# Linux_board_va_1.net
KiCad netlist of a schematic drawn in Altium Designer
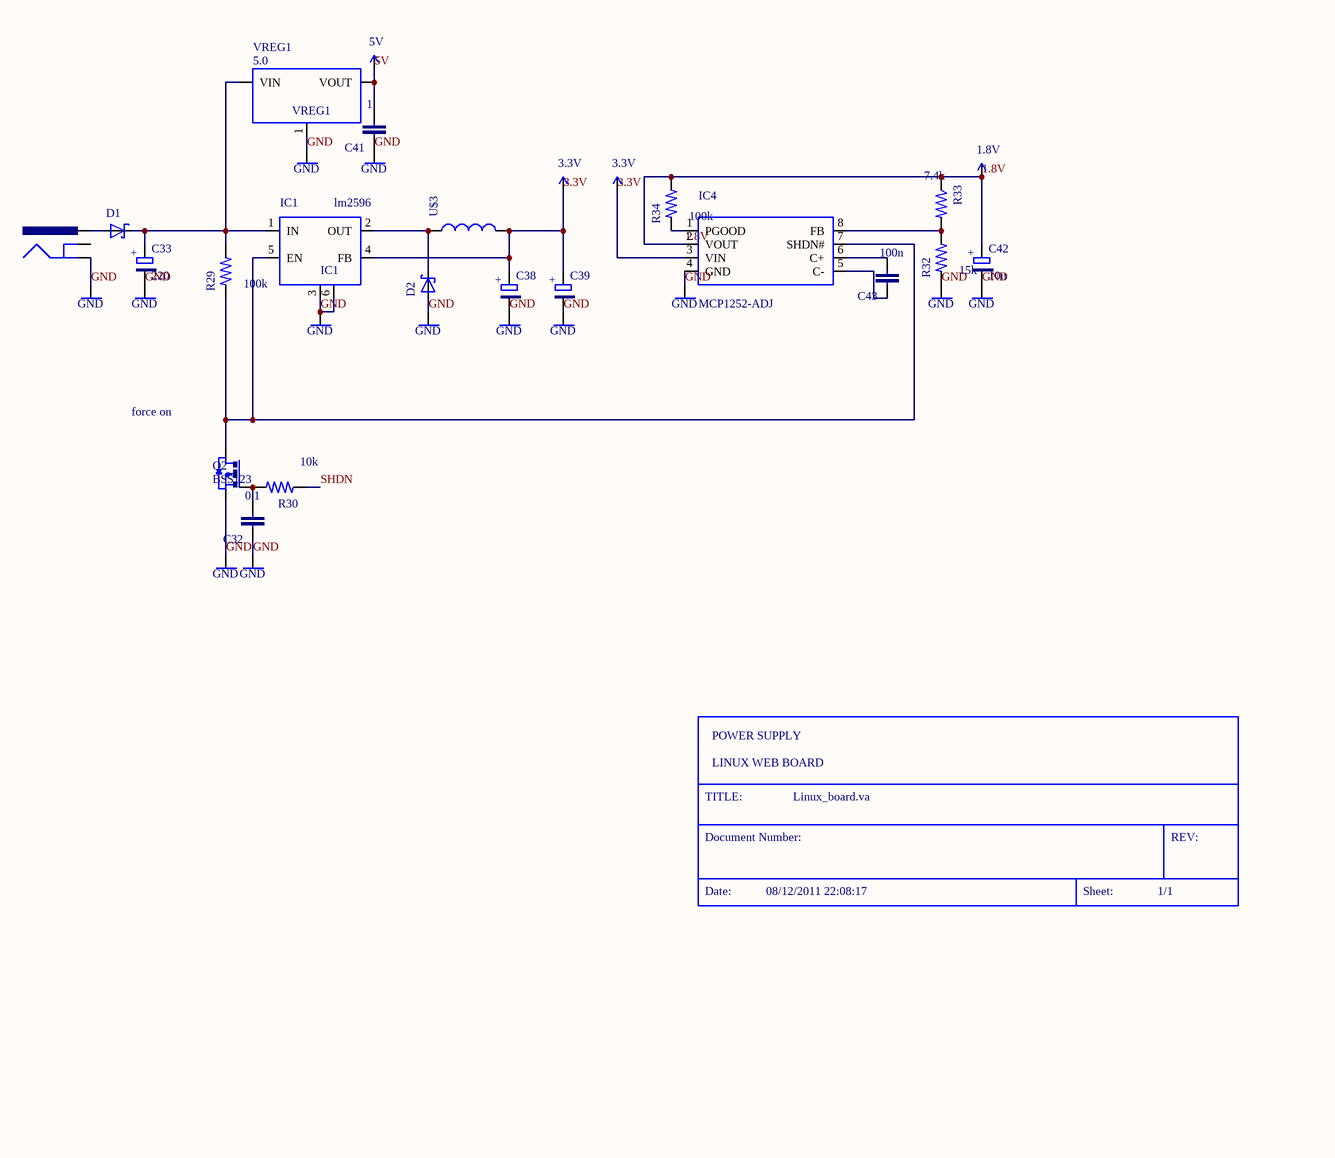
[diagram p0: Linux_board.va_1.SchDoc, top middle]
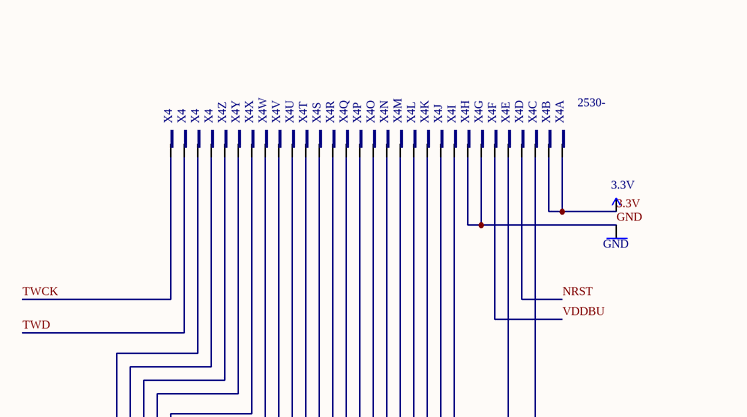
[diagram p1: Linux_board.va_1.SchDoc, top right]
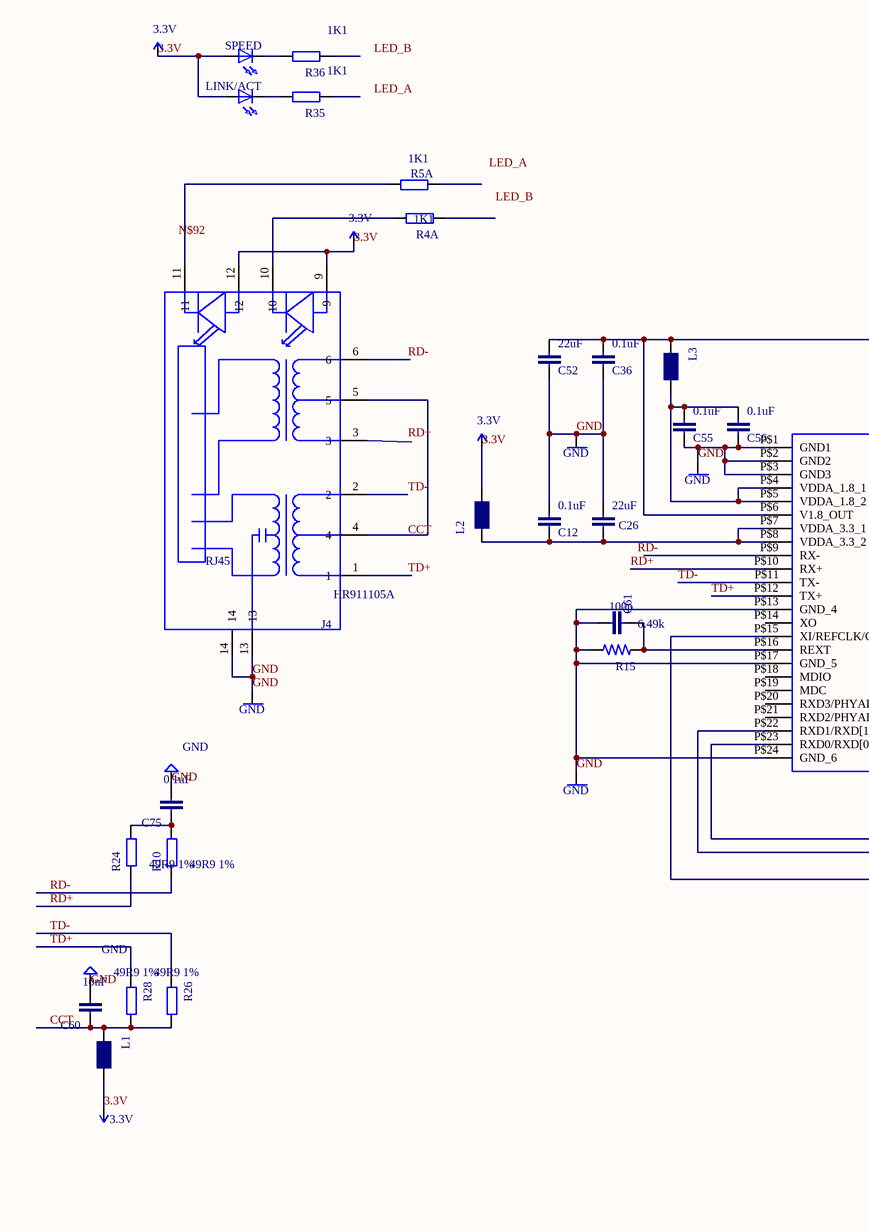
[diagram p2: Linux_board.va_1.SchDoc, bottom left]
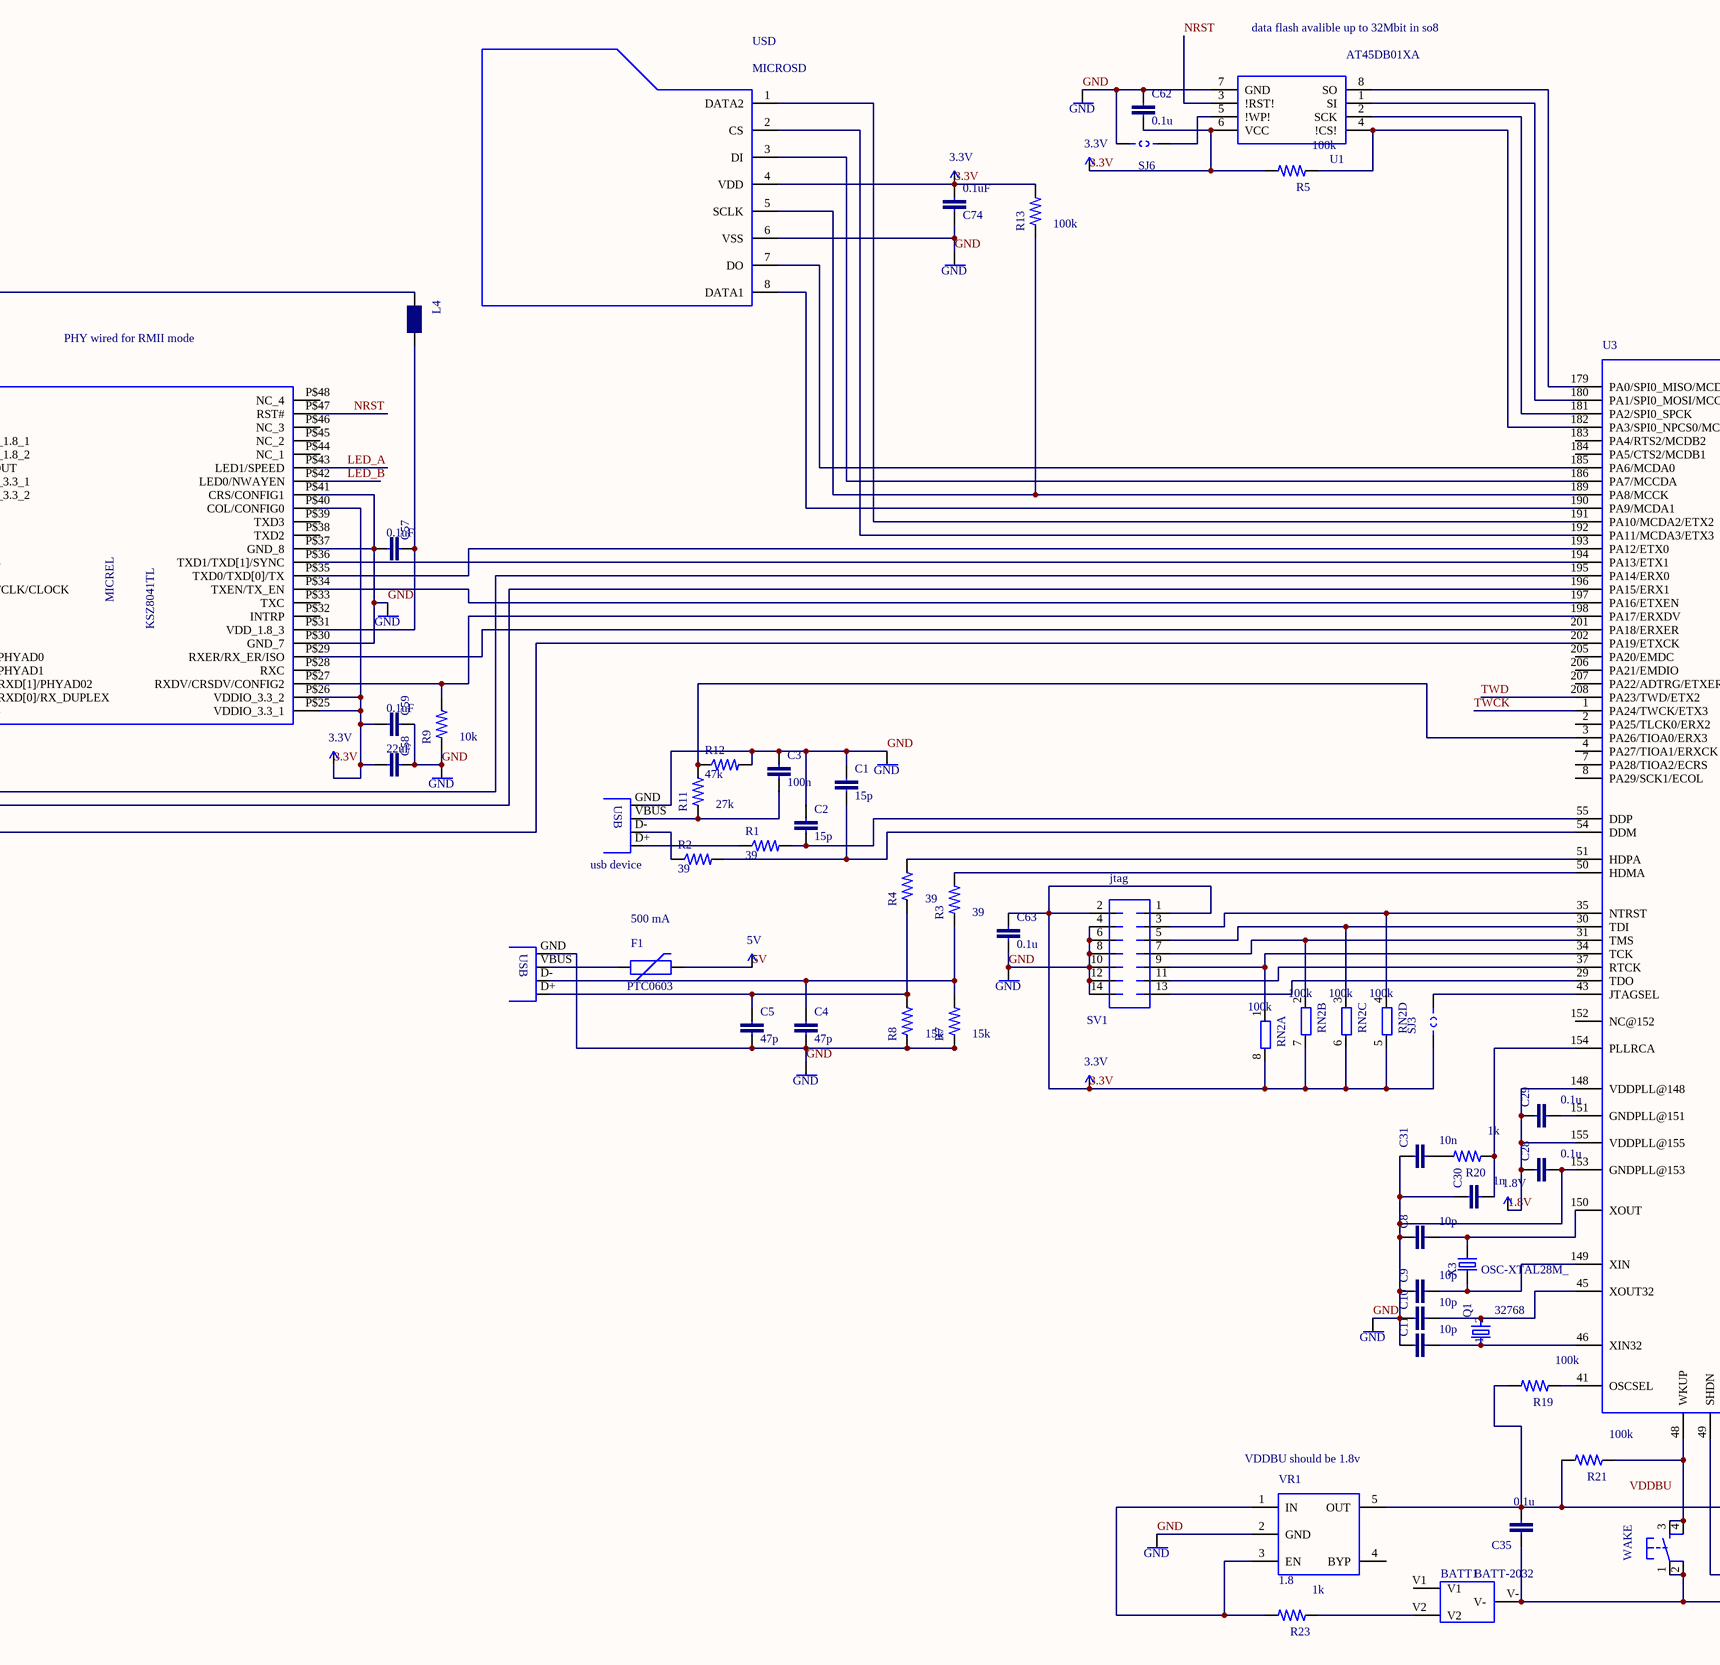
[diagram p3: Linux_board.va_1.SchDoc, bottom middle]
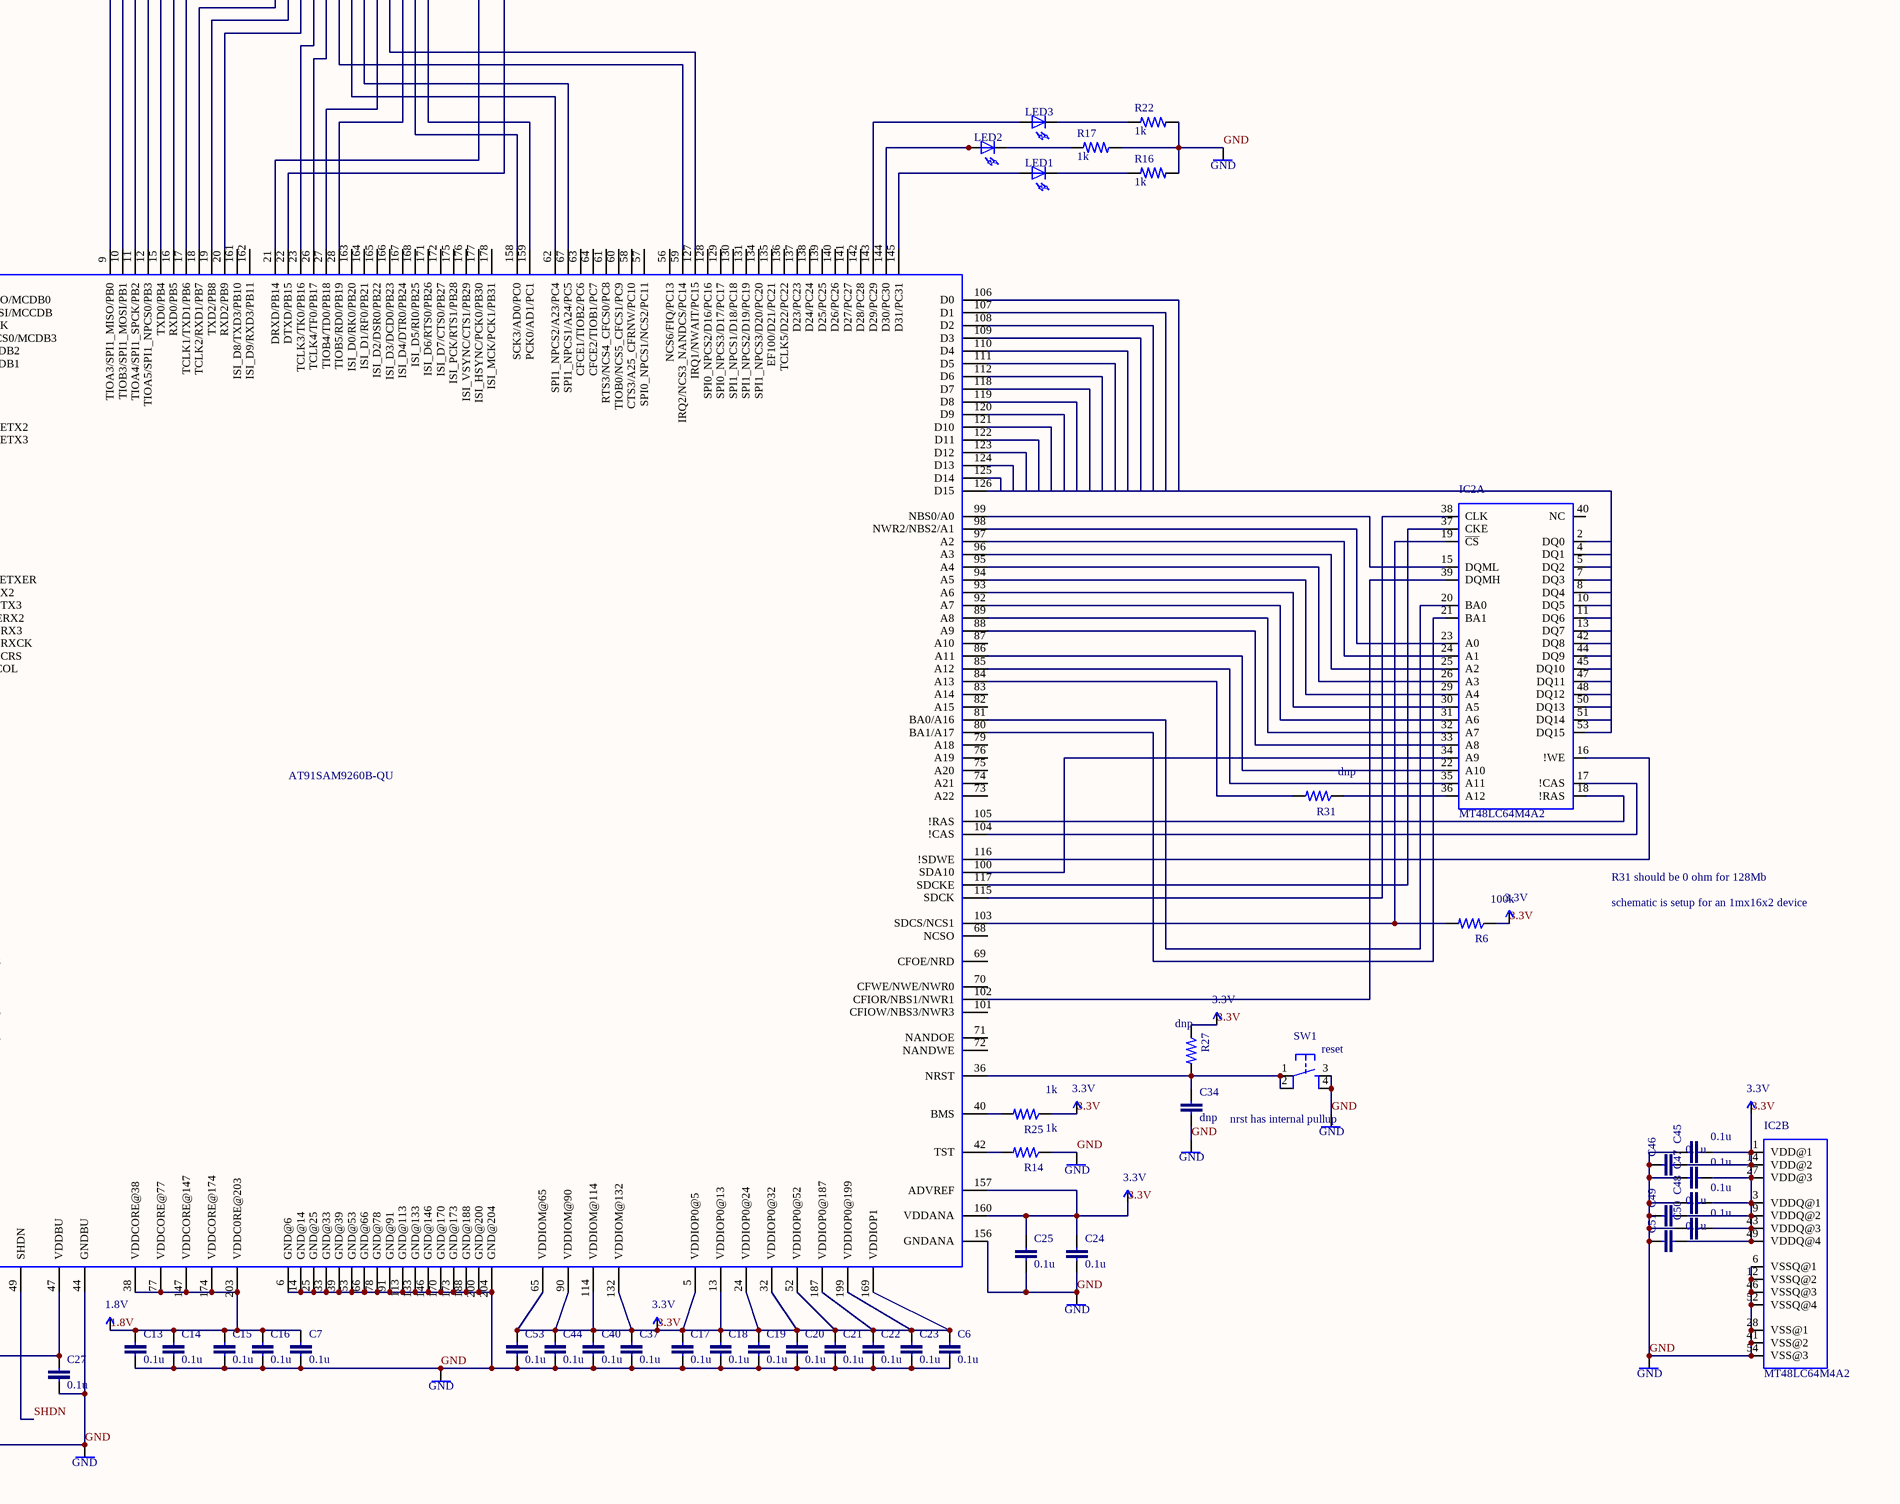
[diagram p4: Linux_board.va_1.SchDoc, bottom right]

(export (version "E")
  (design (tool "Eeschema 10.0.6"))
  (components
    (comp (ref "BATT1")
      (value "BATT-2032")
      (footprint "2032")
      (libsource (lib "dp_devices") (part "BATT-2032"))
    )
    (comp (ref "C1") (value "15p") (footprint "0603-CAP") (libsource (lib "SparkFun") (part "CAP0603-CAP")))
    (comp (ref "C2") (value "15p") (footprint "0603-CAP") (libsource (lib "SparkFun") (part "CAP0603-CAP")))
    (comp (ref "C3") (value "100n") (footprint "0603-CAP") (libsource (lib "SparkFun") (part "CAP0603-CAP")))
    (comp (ref "C4") (value "47p") (footprint "0603-CAP") (libsource (lib "SparkFun") (part "CAP0603-CAP")))
    (comp (ref "C5") (value "47p") (footprint "0603-CAP") (libsource (lib "SparkFun") (part "CAP0603-CAP")))
    (comp (ref "C6") (value "0.1u") (footprint "0603-CAP") (libsource (lib "SparkFun") (part "CAP0603-CAP")))
    (comp (ref "C7") (value "0.1u") (footprint "0603-CAP") (libsource (lib "SparkFun") (part "CAP0603-CAP")))
    (comp (ref "C8") (value "10p") (footprint "0603-CAP") (libsource (lib "SparkFun") (part "CAP0603-CAP")))
    (comp (ref "C9") (value "10p") (footprint "0603-CAP") (libsource (lib "SparkFun") (part "CAP0603-CAP")))
    (comp (ref "C10") (value "10p") (footprint "0603-CAP") (libsource (lib "SparkFun") (part "CAP0603-CAP")))
    (comp (ref "C11") (value "10p") (footprint "0603-CAP") (libsource (lib "SparkFun") (part "CAP0603-CAP")))
    (comp (ref "C12") (value "0.1uF") (footprint "C0603") (libsource (lib "rcl") (part "C-EUC0603")))
    (comp (ref "C13") (value "0.1u") (footprint "0603-CAP") (libsource (lib "SparkFun") (part "CAP0603-CAP")))
    (comp (ref "C14") (value "0.1u") (footprint "0603-CAP") (libsource (lib "SparkFun") (part "CAP0603-CAP")))
    (comp (ref "C15") (value "0.1u") (footprint "0603-CAP") (libsource (lib "SparkFun") (part "CAP0603-CAP")))
    (comp (ref "C16") (value "0.1u") (footprint "0603-CAP") (libsource (lib "SparkFun") (part "CAP0603-CAP")))
    (comp (ref "C17") (value "0.1u") (footprint "0603-CAP") (libsource (lib "SparkFun") (part "CAP0603-CAP")))
    (comp (ref "C18") (value "0.1u") (footprint "0603-CAP") (libsource (lib "SparkFun") (part "CAP0603-CAP")))
    (comp (ref "C19") (value "0.1u") (footprint "0603-CAP") (libsource (lib "SparkFun") (part "CAP0603-CAP")))
    (comp (ref "C20") (value "0.1u") (footprint "0603-CAP") (libsource (lib "SparkFun") (part "CAP0603-CAP")))
    (comp (ref "C21") (value "0.1u") (footprint "0603-CAP") (libsource (lib "SparkFun") (part "CAP0603-CAP")))
    (comp (ref "C22") (value "0.1u") (footprint "0603-CAP") (libsource (lib "SparkFun") (part "CAP0603-CAP")))
    (comp (ref "C23") (value "0.1u") (footprint "0603-CAP") (libsource (lib "SparkFun") (part "CAP0603-CAP")))
    (comp (ref "C24") (value "0.1u") (footprint "0603-CAP") (libsource (lib "SparkFun") (part "CAP0603-CAP")))
    (comp (ref "C25") (value "0.1u") (footprint "0603-CAP") (libsource (lib "SparkFun") (part "CAP0603-CAP")))
    (comp (ref "C26") (value "22uF") (footprint "C0603") (libsource (lib "rcl") (part "C-EUC0603")))
    (comp (ref "C27") (value "0.1u") (footprint "0603-CAP") (libsource (lib "SparkFun") (part "CAP0603-CAP")))
    (comp (ref "C28") (value "0.1u") (footprint "0603-CAP") (libsource (lib "SparkFun") (part "CAP0603-CAP")))
    (comp (ref "C29") (value "0.1u") (footprint "0603-CAP") (libsource (lib "SparkFun") (part "CAP0603-CAP")))
    (comp (ref "C30") (value "1n") (footprint "0603-CAP") (libsource (lib "SparkFun") (part "CAP0603-CAP")))
    (comp (ref "C31") (value "10n") (footprint "0603-CAP") (libsource (lib "SparkFun") (part "CAP0603-CAP")))
    (comp (ref "C32") (value "0.1") (footprint "C603") (libsource (lib "dp_devices") (part "CAPC603")))
    (comp (ref "C33") (value "220") (footprint "SMC_B") (libsource (lib "dp_devices") (part "CAP_POLSMC_B")))
    (comp (ref "C34") (value "dnp") (footprint "0603-CAP") (libsource (lib "SparkFun") (part "CAP0603-CAP")))
    (comp (ref "C35") (value "0.1u") (footprint "0603-CAP") (libsource (lib "SparkFun") (part "CAP0603-CAP")))
    (comp (ref "C36") (value "0.1uF") (footprint "C0603") (libsource (lib "rcl") (part "C-EUC0603")))
    (comp (ref "C37") (value "0.1u") (footprint "0603-CAP") (libsource (lib "SparkFun") (part "CAP0603-CAP")))
    (comp (ref "C38") (value "~") (footprint "CASE_A") (libsource (lib "dp_devices") (part "CAP_POLCASE_A")))
    (comp (ref "C39") (value "~") (footprint "SMC_B") (libsource (lib "dp_devices") (part "CAP_POLSMC_B")))
    (comp (ref "C40") (value "0.1u") (footprint "0603-CAP") (libsource (lib "SparkFun") (part "CAP0603-CAP")))
    (comp (ref "C41") (value "1") (footprint "C603") (libsource (lib "dp_devices") (part "CAPC603")))
    (comp (ref "C42") (value "10u") (footprint "SMC_B") (libsource (lib "dp_devices") (part "CAP_POLSMC_B")))
    (comp (ref "C43") (value "100n") (footprint "C603") (libsource (lib "dp_devices") (part "CAPC603")))
    (comp (ref "C44") (value "0.1u") (footprint "0603-CAP") (libsource (lib "SparkFun") (part "CAP0603-CAP")))
    (comp (ref "C45") (value "0.1u") (footprint "0603-CAP") (libsource (lib "SparkFun") (part "CAP0603-CAP")))
    (comp (ref "C46") (value "0.1u") (footprint "0603-CAP") (libsource (lib "SparkFun") (part "CAP0603-CAP")))
    (comp (ref "C47") (value "0.1u") (footprint "0603-CAP") (libsource (lib "SparkFun") (part "CAP0603-CAP")))
    (comp (ref "C48") (value "0.1u") (footprint "0603-CAP") (libsource (lib "SparkFun") (part "CAP0603-CAP")))
    (comp (ref "C49") (value "0.1u") (footprint "0603-CAP") (libsource (lib "SparkFun") (part "CAP0603-CAP")))
    (comp (ref "C50") (value "0.1u") (footprint "0603-CAP") (libsource (lib "SparkFun") (part "CAP0603-CAP")))
    (comp (ref "C51") (value "0.1u") (footprint "0603-CAP") (libsource (lib "SparkFun") (part "CAP0603-CAP")))
    (comp (ref "C52") (value "22uF") (footprint "C0603") (libsource (lib "rcl") (part "C-EUC0603")))
    (comp (ref "C53") (value "0.1u") (footprint "0603-CAP") (libsource (lib "SparkFun") (part "CAP0603-CAP")))
    (comp (ref "C55") (value "0.1uF") (footprint "C0603") (libsource (lib "rcl") (part "C-EUC0603")))
    (comp (ref "C56") (value "0.1uF") (footprint "C0603") (libsource (lib "rcl") (part "C-EUC0603")))
    (comp (ref "C57") (value "0.1uF") (footprint "C0603") (libsource (lib "rcl") (part "C-EUC0603")))
    (comp (ref "C58") (value "22uF") (footprint "C0603") (libsource (lib "rcl") (part "C-EUC0603")))
    (comp (ref "C59") (value "0.1uF") (footprint "C0603") (libsource (lib "rcl") (part "C-EUC0603")))
    (comp (ref "C60") (value "10uF") (footprint "C0603") (libsource (lib "rcl") (part "C-EUC0603")))
    (comp (ref "C61") (value "100p") (footprint "C0603") (libsource (lib "rcl") (part "C-EUC0603")))
    (comp (ref "C62") (value "0.1u") (footprint "0603-CAP") (libsource (lib "SparkFun") (part "CAP0603-CAP")))
    (comp (ref "C63") (value "0.1u") (footprint "0603-CAP") (libsource (lib "SparkFun") (part "CAP0603-CAP")))
    (comp (ref "C74") (value "0.1uF") (footprint "C0603") (libsource (lib "rcl") (part "C-EUC0603")))
    (comp (ref "C75") (value "0.1uF") (footprint "C0603") (libsource (lib "rcl") (part "C-EUC0603")))
    (comp (ref "D1") (value "~") (footprint "SMB") (libsource (lib "diode") (part "SCHOTTKY-DIODESMD")))
    (comp (ref "D2") (value "~") (footprint "SMB") (libsource (lib "") (part "SCHOTTKY-DIODESMD_1")))
    (comp (ref "F1") (value "PTC0603") (footprint "0603") (libsource (lib "SparkFun") (part "PTC0603")))
    (comp (ref "FRAME1") (value "~") (libsource (lib "") (part "FRAME_A_L_1")))
    (comp (ref "GND1") (value "GND") (libsource (lib "supply1") (part "GND")))
    (comp (ref "GND2") (value "GND") (libsource (lib "supply1") (part "GND")))
    (comp (ref "GND3") (value "GND") (libsource (lib "supply1") (part "GND")))
    (comp (ref "GND4") (value "GND") (libsource (lib "supply1") (part "GND")))
    (comp (ref "GND6") (value "GND") (libsource (lib "supply1") (part "GND")))
    (comp (ref "GND7") (value "GND") (libsource (lib "supply1") (part "GND")))
    (comp (ref "GND8") (value "GND") (libsource (lib "supply1") (part "GND")))
    (comp (ref "GND9") (value "GND") (libsource (lib "supply1") (part "GND")))
    (comp (ref "GND10") (value "GND") (libsource (lib "") (part "GND_1")))
    (comp (ref "GND11") (value "GND") (libsource (lib "") (part "GND_1")))
    (comp (ref "GND12") (value "GND") (libsource (lib "supply1") (part "GND")))
    (comp (ref "GND13") (value "GND") (libsource (lib "") (part "GND_1")))
    (comp (ref "GND14") (value "GND") (libsource (lib "supply1") (part "GND")))
    (comp (ref "GND15") (value "GND") (libsource (lib "") (part "GND_1")))
    (comp (ref "GND16") (value "GND") (libsource (lib "supply1") (part "GND")))
    (comp (ref "GND17") (value "GND") (libsource (lib "supply1") (part "GND")))
    (comp (ref "GND18") (value "GND") (libsource (lib "supply1") (part "GND")))
    (comp (ref "GND19") (value "GND") (libsource (lib "supply1") (part "GND")))
    (comp (ref "GND20") (value "GND") (libsource (lib "supply1") (part "GND")))
    (comp (ref "GND21") (value "GND") (libsource (lib "supply1") (part "GND")))
    (comp (ref "GND22") (value "GND") (libsource (lib "supply1") (part "GND")))
    (comp (ref "GND23") (value "GND") (libsource (lib "") (part "GND_1")))
    (comp (ref "GND24") (value "GND") (libsource (lib "") (part "GND_1")))
    (comp (ref "GND25") (value "GND") (libsource (lib "supply1") (part "GND")))
    (comp (ref "GND26") (value "GND") (libsource (lib "supply1") (part "GND")))
    (comp (ref "GND27") (value "GND") (libsource (lib "supply1") (part "GND")))
    (comp (ref "GND28") (value "GND") (libsource (lib "supply1") (part "GND")))
    (comp (ref "GND29") (value "GND") (libsource (lib "supply1") (part "GND")))
    (comp (ref "GND30") (value "GND") (libsource (lib "supply1") (part "GND")))
    (comp (ref "GND31") (value "GND") (libsource (lib "supply1") (part "GND")))
    (comp (ref "GND32") (value "GND") (libsource (lib "supply1") (part "GND")))
    (comp (ref "GND33") (value "GND") (libsource (lib "supply1") (part "GND")))
    (comp (ref "GND34") (value "GND") (libsource (lib "supply1") (part "GND")))
    (comp (ref "GND35") (value "GND") (libsource (lib "supply1") (part "GND")))
    (comp (ref "GND36") (value "GND") (libsource (lib "supply1") (part "GND")))
    (comp (ref "IC1") (value "lm2596") (footprint "TO263-5") (libsource (lib "linear") (part "LM2596S")))
    (comp (ref "IC2")
      (value "MT48LC64M4A2")
      (footprint "TSOP54-400")
      (libsource (lib "memory-micron") (part "MT48LC64M4A2"))
    )
    (comp (ref "IC4")
      (value "MCP1252-ADJ")
      (footprint "MSOP8")
      (libsource (lib "microchip-dspic") (part "MCP1252-ADJ"))
    )
    (comp (ref "J4") (value "RJ45") (footprint "HR911105A") (libsource (lib "CONNECTER") (part "HR911105A")))
    (comp (ref "JP1") (value "~") (footprint "STAND-OFF") (libsource (lib "SparkFun") (part "STAND-OFF")))
    (comp (ref "JP2") (value "~") (footprint "STAND-OFF") (libsource (lib "SparkFun") (part "STAND-OFF")))
    (comp (ref "JP3") (value "~") (footprint "STAND-OFF") (libsource (lib "SparkFun") (part "STAND-OFF")))
    (comp (ref "JP4") (value "~") (footprint "STAND-OFF") (libsource (lib "SparkFun") (part "STAND-OFF")))
    (comp (ref "L1")
      (value "~")
      (footprint "WE-KI_0805_B")
      (libsource (lib "wuerth-elektronik") (part "WE-KIL_0805"))
    )
    (comp (ref "L2")
      (value "~")
      (footprint "WE-KI_0805_B")
      (libsource (lib "wuerth-elektronik") (part "WE-KIL_0805"))
    )
    (comp (ref "L3")
      (value "~")
      (footprint "WE-KI_0805_B")
      (libsource (lib "wuerth-elektronik") (part "WE-KIL_0805"))
    )
    (comp (ref "L4")
      (value "~")
      (footprint "WE-KI_0805_B")
      (libsource (lib "wuerth-elektronik") (part "WE-KIL_0805"))
    )
    (comp (ref "LED1")
      (value "~")
      (footprint "CHIPLED_0805")
      (libsource (lib "led") (part "LEDCHIPLED_0805"))
    )
    (comp (ref "LED2")
      (value "~")
      (footprint "CHIPLED_0805")
      (libsource (lib "led") (part "LEDCHIPLED_0805"))
    )
    (comp (ref "LED3")
      (value "~")
      (footprint "CHIPLED_0805")
      (libsource (lib "led") (part "LEDCHIPLED_0805"))
    )
    (comp (ref "LINK/ACT")
      (value "~")
      (footprint "CHIPLED_0805")
      (libsource (lib "") (part "LEDCHIPLED_0805_1"))
    )
    (comp (ref "P+1") (value "3.3V") (libsource (lib "SparkFun") (part "3.3V")))
    (comp (ref "P+2") (value "3.3V") (libsource (lib "SparkFun") (part "3.3V")))
    (comp (ref "P+3") (value "3.3V") (libsource (lib "SparkFun") (part "3.3V")))
    (comp (ref "P+4") (value "3.3V") (libsource (lib "SparkFun") (part "3.3V")))
    (comp (ref "P+5") (value "3.3V") (libsource (lib "SparkFun") (part "3.3V")))
    (comp (ref "P+6") (value "3.3V") (libsource (lib "SparkFun") (part "3.3V")))
    (comp (ref "P+7") (value "3.3V") (libsource (lib "SparkFun") (part "3.3V")))
    (comp (ref "P+8") (value "3.3V") (libsource (lib "SparkFun") (part "3.3V")))
    (comp (ref "P+9") (value "3.3V") (libsource (lib "SparkFun") (part "3.3V")))
    (comp (ref "P+10") (value "3.3V") (libsource (lib "SparkFun") (part "3.3V")))
    (comp (ref "P+11") (value "3.3V") (libsource (lib "SparkFun") (part "3.3V")))
    (comp (ref "P+12") (value "3.3V") (libsource (lib "SparkFun") (part "3.3V")))
    (comp (ref "P+13") (value "3.3V") (libsource (lib "SparkFun") (part "3.3V")))
    (comp (ref "P+14") (value "3.3V") (libsource (lib "SparkFun") (part "3.3V")))
    (comp (ref "P+15") (value "3.3V") (libsource (lib "SparkFun") (part "3.3V")))
    (comp (ref "P+16") (value "3.3V") (libsource (lib "SparkFun") (part "3.3V")))
    (comp (ref "P+17") (value "3.3V") (libsource (lib "SparkFun") (part "3.3V")))
    (comp (ref "Q1") (value "32768") (footprint "TC26H") (libsource (lib "crystal") (part "CRYSTALTC26H")))
    (comp (ref "Q2")
      (value "BSS123")
      (footprint "SOT23")
      (libsource (lib "transistor-small-signal") (part "BSS123"))
    )
    (comp (ref "R1") (value "39") (footprint "R0603") (libsource (lib "") (part "R-US_R0603_1")))
    (comp (ref "R2") (value "39") (footprint "R0603") (libsource (lib "") (part "R-US_R0603_1")))
    (comp (ref "R3") (value "39") (footprint "R0603") (libsource (lib "resistor") (part "R-US_R0603")))
    (comp (ref "R4") (value "39") (footprint "R0603") (libsource (lib "resistor") (part "R-US_R0603")))
    (comp (ref "R4A") (value "1K1") (footprint "R0603") (libsource (lib "rcl") (part "R-EU_R0603")))
    (comp (ref "R5") (value "100k") (footprint "R0603") (libsource (lib "resistor") (part "R-US_R0603")))
    (comp (ref "R5A") (value "1K1") (footprint "R0603") (libsource (lib "rcl") (part "R-EU_R0603")))
    (comp (ref "R6") (value "100k") (footprint "R0603") (libsource (lib "") (part "R-US_R0603_1")))
    (comp (ref "R7") (value "15k") (footprint "R0603") (libsource (lib "resistor") (part "R-US_R0603")))
    (comp (ref "R8") (value "15k") (footprint "R0603") (libsource (lib "resistor") (part "R-US_R0603")))
    (comp (ref "R9") (value "10k") (footprint "R0603") (libsource (lib "resistor") (part "R-US_R0603")))
    (comp (ref "R10") (value "49R9 1%") (footprint "R0603") (libsource (lib "") (part "R-EU_R0603_1")))
    (comp (ref "R11") (value "27k") (footprint "R0603") (libsource (lib "resistor") (part "R-US_R0603")))
    (comp (ref "R12") (value "47k") (footprint "R0603") (libsource (lib "") (part "R-US_R0603_1")))
    (comp (ref "R13") (value "100k") (footprint "R0603") (libsource (lib "resistor") (part "R-US_R0603")))
    (comp (ref "R14") (value "1k") (footprint "R0603") (libsource (lib "") (part "R-US_R0603_1")))
    (comp (ref "R15") (value "6.49k") (footprint "R0603") (libsource (lib "resistor") (part "R-US_R0603")))
    (comp (ref "R16") (value "1k") (footprint "R0603") (libsource (lib "resistor") (part "R-US_R0603")))
    (comp (ref "R17") (value "1k") (footprint "R0603") (libsource (lib "resistor") (part "R-US_R0603")))
    (comp (ref "R19") (value "100k") (footprint "R0603") (libsource (lib "resistor") (part "R-US_R0603")))
    (comp (ref "R20") (value "1k") (footprint "R0603") (libsource (lib "resistor") (part "R-US_R0603")))
    (comp (ref "R21") (value "100k") (footprint "R0603") (libsource (lib "resistor") (part "R-US_R0603")))
    (comp (ref "R22") (value "1k") (footprint "R0603") (libsource (lib "resistor") (part "R-US_R0603")))
    (comp (ref "R23") (value "1k") (footprint "R0603") (libsource (lib "resistor") (part "R-US_R0603")))
    (comp (ref "R24") (value "49R9 1%") (footprint "R0603") (libsource (lib "") (part "R-EU_R0603_1")))
    (comp (ref "R25") (value "1k") (footprint "R0603") (libsource (lib "") (part "R-US_R0603_1")))
    (comp (ref "R26") (value "49R9 1%") (footprint "R0603") (libsource (lib "rcl") (part "R-EU_R0603")))
    (comp (ref "R27") (value "dnp") (footprint "R0603") (libsource (lib "") (part "R-US_R0603_1")))
    (comp (ref "R28") (value "49R9 1%") (footprint "R0603") (libsource (lib "rcl") (part "R-EU_R0603")))
    (comp (ref "R29") (value "100k") (footprint "R0603") (libsource (lib "resistor") (part "R-US_R0603")))
    (comp (ref "R30") (value "10k") (footprint "R0603") (libsource (lib "resistor") (part "R-US_R0603")))
    (comp (ref "R31") (value "dnp") (footprint "R0603") (libsource (lib "") (part "R-US_R0603_1")))
    (comp (ref "R32") (value "15k") (footprint "R0603") (libsource (lib "resistor") (part "R-US_R0603")))
    (comp (ref "R33") (value "7.4k") (footprint "R0603") (libsource (lib "") (part "R-US_R0603_1")))
    (comp (ref "R34") (value "100k") (footprint "R0603") (libsource (lib "resistor") (part "R-US_R0603")))
    (comp (ref "R35") (value "1K1") (footprint "R0603") (libsource (lib "rcl") (part "R-EU_R0603")))
    (comp (ref "R36") (value "1K1") (footprint "R0603") (libsource (lib "rcl") (part "R-EU_R0603")))
    (comp (ref "RN2") (value "100k") (footprint "RN8P-4R-CRA06S") (libsource (lib "") (part "RNETWORK_3")))
    (comp (ref "SJ3") (value "~") (footprint "SJ_2S-NO") (libsource (lib "SparkFun") (part "SOLDERJUMPERNO")))
    (comp (ref "SJ6") (value "~") (footprint "SJ_2S-NO") (libsource (lib "SparkFun") (part "SOLDERJUMPERNO")))
    (comp (ref "SPEED")
      (value "~")
      (footprint "CHIPLED_0805")
      (libsource (lib "") (part "LEDCHIPLED_0805_1"))
    )
    (comp (ref "SV1") (value "jtag") (footprint "MA07-2") (libsource (lib "con-lstb") (part "MA07-2")))
    (comp (ref "SW1")
      (value "reset")
      (footprint "TACT_SWITCH_SMALL")
      (libsource (lib "dp_devices") (part "SW-SMD-SMALL"))
    )
    (comp (ref "U$1") (value "~") (footprint "48PIN-TQFN") (libsource (lib "micrelphy") (part "KSZ8041TL")))
    (comp (ref "U$2")
      (value "~")
      (footprint "POWER_JACK_SMD")
      (libsource (lib "SparkFun-3-2-07") (part "POWER_JACKSMD"))
    )
    (comp (ref "U$3") (value "~") (footprint "CDRH125") (libsource (lib "SparkFun") (part "INDUCTORPWR")))
    (comp (ref "U$4") (value "1.8V") (libsource (lib "SparkFun") (part "1.8V")))
    (comp (ref "U$5") (value "1.8V") (libsource (lib "SparkFun") (part "1.8V")))
    (comp (ref "U$6") (value "1.8V") (libsource (lib "SparkFun") (part "1.8V")))
    (comp (ref "U$7") (value "5V") (libsource (lib "SparkFun") (part "5V")))
    (comp (ref "U$10") (value "5V") (libsource (lib "SparkFun") (part "5V")))
    (comp (ref "U1")
      (value "AT45DB01XA")
      (footprint "SO08W")
      (libsource (lib "memory-atmel") (part "AT45DB01XA"))
    )
    (comp (ref "U3")
      (value "AT91SAM9260B-QU")
      (footprint "PQFP208")
      (libsource (lib "atmel-arm") (part "AT91SAM9260B-QU"))
    )
    (comp (ref "USD") (value "MICROSD") (footprint "MICROSD") (libsource (lib "Seeed") (part "MICROSD")))
    (comp (ref "V7") (value "GND") (libsource (lib "supply2") (part "GND")))
    (comp (ref "V8") (value "GND") (libsource (lib "supply2") (part "GND")))
    (comp (ref "VR1") (value "1.8") (footprint "SOT-23-5") (libsource (lib "dp_devices") (part "MIC5205")))
    (comp (ref "VREG1")
      (value "5.0")
      (footprint "SOT223")
      (libsource (lib "dp_devices") (part "LD1117-3.3SOT223"))
    )
    (comp (ref "WAKE")
      (value "~")
      (footprint "TACT_SWITCH_SMALL")
      (libsource (lib "dp_devices") (part "SW-SMD-SMALL"))
    )
    (comp (ref "X1") (value "~") (footprint "USB-MB-S") (libsource (lib "con-usb") (part "USB-MB-S")))
    (comp (ref "X2") (value "~") (footprint "USB-A-H") (libsource (lib "con-usb") (part "USB-A-H")))
    (comp (ref "X3")
      (value "OSC-XTAL28M_")
      (footprint "5X8")
      (libsource (lib "dp_devices") (part "OSC-XTAL28M_"))
    )
    (comp (ref "X4") (value "2530-") (footprint "PAK100/2500-30") (libsource (lib "") (part "2530-_24")))
  )
  (nets
    (net (code "1") (name "/1.8V") (class "Default")
      (node (ref "C13") (pin "1") (pinfunction "1_1") (pintype "passive"))
      (node (ref "C14") (pin "1") (pinfunction "1_1") (pintype "passive"))
      (node (ref "C15") (pin "1") (pinfunction "1_1") (pintype "passive"))
      (node (ref "C16") (pin "1") (pinfunction "1_1") (pintype "passive"))
      (node (ref "C28") (pin "1") (pinfunction "1_1") (pintype "passive"))
      (node (ref "C29") (pin "1") (pinfunction "1_1") (pintype "passive"))
      (node (ref "C42") (pin "+") (pinfunction "+_+") (pintype "passive"))
      (node (ref "C7") (pin "1") (pinfunction "1_1") (pintype "passive"))
      (node (ref "IC4") (pin "2") (pinfunction "VOUT_2") (pintype "passive"))
      (node (ref "R33") (pin "1") (pinfunction "1_1") (pintype "passive"))
      (node (ref "R34") (pin "2") (pinfunction "2_2") (pintype "passive"))
      (node (ref "U$4") (pin "0") (pinfunction "1.8V_0") (pintype "passive"))
      (node (ref "U$5") (pin "0") (pinfunction "1.8V_0") (pintype "passive"))
      (node (ref "U$6") (pin "0") (pinfunction "1.8V_0") (pintype "passive"))
      (node (ref "U3") (pin "147") (pinfunction "VDDCORE@147_147") (pintype "passive"))
      (node (ref "U3") (pin "148") (pinfunction "VDDPLL@148_148") (pintype "passive"))
      (node (ref "U3") (pin "155") (pinfunction "VDDPLL@155_155") (pintype "passive"))
      (node (ref "U3") (pin "174") (pinfunction "VDDCORE@174_174") (pintype "passive"))
      (node (ref "U3") (pin "203") (pinfunction "VDDC0RE@203_203") (pintype "passive"))
      (node (ref "U3") (pin "38") (pinfunction "VDDCORE@38_38") (pintype "passive"))
      (node (ref "U3") (pin "77") (pinfunction "VDDCORE@77_77") (pintype "passive"))
    )
    (net (code "2") (name "/3.3V") (class "Default")
      (node (ref "C17") (pin "1") (pinfunction "1_1") (pintype "passive"))
      (node (ref "C18") (pin "1") (pinfunction "1_1") (pintype "passive"))
      (node (ref "C19") (pin "1") (pinfunction "1_1") (pintype "passive"))
      (node (ref "C20") (pin "1") (pinfunction "1_1") (pintype "passive"))
      (node (ref "C21") (pin "1") (pinfunction "1_1") (pintype "passive"))
      (node (ref "C22") (pin "1") (pinfunction "1_1") (pintype "passive"))
      (node (ref "C23") (pin "1") (pinfunction "1_1") (pintype "passive"))
      (node (ref "C24") (pin "1") (pinfunction "1_1") (pintype "passive"))
      (node (ref "C25") (pin "1") (pinfunction "1_1") (pintype "passive"))
      (node (ref "C37") (pin "1") (pinfunction "1_1") (pintype "passive"))
      (node (ref "C38") (pin "+") (pinfunction "+_+") (pintype "passive"))
      (node (ref "C39") (pin "+") (pinfunction "+_+") (pintype "passive"))
      (node (ref "C40") (pin "1") (pinfunction "1_1") (pintype "passive"))
      (node (ref "C44") (pin "1") (pinfunction "1_1") (pintype "passive"))
      (node (ref "C45") (pin "2") (pinfunction "2_2") (pintype "passive"))
      (node (ref "C46") (pin "2") (pinfunction "2_2") (pintype "passive"))
      (node (ref "C47") (pin "2") (pinfunction "2_2") (pintype "passive"))
      (node (ref "C48") (pin "2") (pinfunction "2_2") (pintype "passive"))
      (node (ref "C49") (pin "2") (pinfunction "2_2") (pintype "passive"))
      (node (ref "C50") (pin "2") (pinfunction "2_2") (pintype "passive"))
      (node (ref "C51") (pin "2") (pinfunction "2_2") (pintype "passive"))
      (node (ref "C53") (pin "1") (pinfunction "1_1") (pintype "passive"))
      (node (ref "C58") (pin "1") (pinfunction "1_1") (pintype "passive"))
      (node (ref "C59") (pin "1") (pinfunction "1_1") (pintype "passive"))
      (node (ref "C6") (pin "1") (pinfunction "1_1") (pintype "passive"))
      (node (ref "C62") (pin "2") (pinfunction "2_2") (pintype "passive"))
      (node (ref "C63") (pin "1") (pinfunction "1_1") (pintype "passive"))
      (node (ref "C74") (pin "1") (pinfunction "1_1") (pintype "passive"))
      (node (ref "IC1") (pin "4") (pinfunction "FB_4") (pintype "passive"))
      (node (ref "IC2") (pin "1") (pinfunction "VDD@1_1") (pintype "passive"))
      (node (ref "IC2") (pin "14") (pinfunction "VDD@2_14") (pintype "passive"))
      (node (ref "IC2") (pin "27") (pinfunction "VDD@3_27") (pintype "passive"))
      (node (ref "IC2") (pin "3") (pinfunction "VDDQ@1_3") (pintype "passive"))
      (node (ref "IC2") (pin "43") (pinfunction "VDDQ@3_43") (pintype "passive"))
      (node (ref "IC2") (pin "49") (pinfunction "VDDQ@4_49") (pintype "passive"))
      (node (ref "IC2") (pin "9") (pinfunction "VDDQ@2_9") (pintype "passive"))
      (node (ref "IC4") (pin "3") (pinfunction "VIN_3") (pintype "passive"))
      (node (ref "J4") (pin "12") (pinfunction "12_12") (pintype "passive"))
      (node (ref "J4") (pin "9") (pinfunction "9_9") (pintype "passive"))
      (node (ref "L1") (pin "1") (pinfunction "2_1") (pintype "passive"))
      (node (ref "L2") (pin "1") (pinfunction "2_1") (pintype "passive"))
      (node (ref "LINK/ACT") (pin "A") (pinfunction "A_A") (pintype "passive"))
      (node (ref "P+1") (pin "0") (pinfunction "3.3V_0") (pintype "passive"))
      (node (ref "P+10") (pin "0") (pinfunction "3.3V_0") (pintype "passive"))
      (node (ref "P+11") (pin "0") (pinfunction "3.3V_0") (pintype "passive"))
      (node (ref "P+12") (pin "0") (pinfunction "3.3V_0") (pintype "passive"))
      (node (ref "P+13") (pin "0") (pinfunction "3.3V_0") (pintype "passive"))
      (node (ref "P+14") (pin "0") (pinfunction "3.3V_0") (pintype "passive"))
      (node (ref "P+15") (pin "0") (pinfunction "3.3V_0") (pintype "passive"))
      (node (ref "P+16") (pin "0") (pinfunction "3.3V_0") (pintype "passive"))
      (node (ref "P+17") (pin "0") (pinfunction "3.3V_0") (pintype "passive"))
      (node (ref "P+2") (pin "0") (pinfunction "3.3V_0") (pintype "passive"))
      (node (ref "P+3") (pin "0") (pinfunction "3.3V_0") (pintype "passive"))
      (node (ref "P+4") (pin "0") (pinfunction "3.3V_0") (pintype "passive"))
      (node (ref "P+5") (pin "0") (pinfunction "3.3V_0") (pintype "passive"))
      (node (ref "P+6") (pin "0") (pinfunction "3.3V_0") (pintype "passive"))
      (node (ref "P+7") (pin "0") (pinfunction "3.3V_0") (pintype "passive"))
      (node (ref "P+8") (pin "0") (pinfunction "3.3V_0") (pintype "passive"))
      (node (ref "P+9") (pin "0") (pinfunction "3.3V_0") (pintype "passive"))
      (node (ref "R13") (pin "2") (pinfunction "2_2") (pintype "passive"))
      (node (ref "R25") (pin "1") (pinfunction "1_1") (pintype "passive"))
      (node (ref "R27") (pin "1") (pinfunction "1_1") (pintype "passive"))
      (node (ref "R5") (pin "2") (pinfunction "2_2") (pintype "passive"))
      (node (ref "R6") (pin "1") (pinfunction "1_1") (pintype "passive"))
      (node (ref "RN2") (pin "5") (pinfunction "2_5") (pintype "passive"))
      (node (ref "RN2") (pin "6") (pinfunction "2_6") (pintype "passive"))
      (node (ref "RN2") (pin "7") (pinfunction "2_7") (pintype "passive"))
      (node (ref "RN2") (pin "8") (pinfunction "2_8") (pintype "passive"))
      (node (ref "SJ3") (pin "1") (pinfunction "1_1") (pintype "passive"))
      (node (ref "SPEED") (pin "A") (pinfunction "A_A") (pintype "passive"))
      (node (ref "SV1") (pin "1") (pinfunction "1_1") (pintype "passive"))
      (node (ref "SV1") (pin "2") (pinfunction "2_2") (pintype "passive"))
      (node (ref "U$1") (pin "P$25") (pinfunction "VDDIO_3.3_1_P$25") (pintype "passive"))
      (node (ref "U$1") (pin "P$26") (pinfunction "VDDIO_3.3_2_P$26") (pintype "passive"))
      (node (ref "U$1") (pin "P$40") (pinfunction "COL/CONFIG0_P$40") (pintype "passive"))
      (node (ref "U$3") (pin "2") (pinfunction "2_2") (pintype "passive"))
      (node (ref "U1") (pin "6") (pinfunction "VCC_6") (pintype "passive"))
      (node (ref "U3") (pin "114") (pinfunction "VDDIOM@114_114") (pintype "passive"))
      (node (ref "U3") (pin "13") (pinfunction "VDDIOP0@13_13") (pintype "passive"))
      (node (ref "U3") (pin "132") (pinfunction "VDDIOM@132_132") (pintype "passive"))
      (node (ref "U3") (pin "157") (pinfunction "ADVREF_157") (pintype "passive"))
      (node (ref "U3") (pin "160") (pinfunction "VDDANA_160") (pintype "passive"))
      (node (ref "U3") (pin "169") (pinfunction "VDDIOP1_169") (pintype "passive"))
      (node (ref "U3") (pin "187") (pinfunction "VDDIOP0@187_187") (pintype "passive"))
      (node (ref "U3") (pin "199") (pinfunction "VDDIOP0@199_199") (pintype "passive"))
      (node (ref "U3") (pin "24") (pinfunction "VDDIOP0@24_24") (pintype "passive"))
      (node (ref "U3") (pin "32") (pinfunction "VDDIOP0@32_32") (pintype "passive"))
      (node (ref "U3") (pin "5") (pinfunction "VDDIOP0@5_5") (pintype "passive"))
      (node (ref "U3") (pin "52") (pinfunction "VDDIOP0@52_52") (pintype "passive"))
      (node (ref "U3") (pin "65") (pinfunction "VDDIOM@65_65") (pintype "passive"))
      (node (ref "U3") (pin "90") (pinfunction "VDDIOM@90_90") (pintype "passive"))
      (node (ref "USD") (pin "4") (pinfunction "VDD_4") (pintype "passive"))
      (node (ref "X4") (pin "1") (pinfunction "KL_1") (pintype "passive"))
      (node (ref "X4") (pin "2") (pinfunction "KL_2") (pintype "passive"))
    )
    (net (code "3") (name "/5V") (class "Default")
      (node (ref "C41") (pin "2") (pinfunction "2_2") (pintype "passive"))
      (node (ref "F1") (pin "2") (pinfunction "2_2") (pintype "passive"))
      (node (ref "U$10") (pin "0") (pinfunction "5V_0") (pintype "passive"))
      (node (ref "U$7") (pin "0") (pinfunction "5V_0") (pintype "passive"))
      (node (ref "VREG1") (pin "2") (pinfunction "VOUT_2") (pintype "passive"))
    )
    (net (code "4") (name "/CCT") (class "Default")
      (node (ref "C60") (pin "1") (pinfunction "1_1") (pintype "passive"))
      (node (ref "L1") (pin "2") (pinfunction "1_2") (pintype "passive"))
      (node (ref "R26") (pin "2") (pinfunction "2_2") (pintype "passive"))
      (node (ref "R28") (pin "2") (pinfunction "2_2") (pintype "passive"))
    )
    (net (code "5") (name "/GND") (class "Default")
      (node (ref "BATT1") (pin "V-") (pinfunction "V-_V-") (pintype "passive"))
      (node (ref "C1") (pin "1") (pinfunction "1_1") (pintype "passive"))
      (node (ref "C10") (pin "1") (pinfunction "1_1") (pintype "passive"))
      (node (ref "C11") (pin "1") (pinfunction "1_1") (pintype "passive"))
      (node (ref "C12") (pin "1") (pinfunction "1_1") (pintype "passive"))
      (node (ref "C13") (pin "2") (pinfunction "2_2") (pintype "passive"))
      (node (ref "C14") (pin "2") (pinfunction "2_2") (pintype "passive"))
      (node (ref "C15") (pin "2") (pinfunction "2_2") (pintype "passive"))
      (node (ref "C16") (pin "2") (pinfunction "2_2") (pintype "passive"))
      (node (ref "C17") (pin "2") (pinfunction "2_2") (pintype "passive"))
      (node (ref "C18") (pin "2") (pinfunction "2_2") (pintype "passive"))
      (node (ref "C19") (pin "2") (pinfunction "2_2") (pintype "passive"))
      (node (ref "C2") (pin "1") (pinfunction "1_1") (pintype "passive"))
      (node (ref "C20") (pin "2") (pinfunction "2_2") (pintype "passive"))
      (node (ref "C21") (pin "2") (pinfunction "2_2") (pintype "passive"))
      (node (ref "C22") (pin "2") (pinfunction "2_2") (pintype "passive"))
      (node (ref "C23") (pin "2") (pinfunction "2_2") (pintype "passive"))
      (node (ref "C24") (pin "2") (pinfunction "2_2") (pintype "passive"))
      (node (ref "C25") (pin "2") (pinfunction "2_2") (pintype "passive"))
      (node (ref "C26") (pin "1") (pinfunction "1_1") (pintype "passive"))
      (node (ref "C27") (pin "2") (pinfunction "2_2") (pintype "passive"))
      (node (ref "C28") (pin "2") (pinfunction "2_2") (pintype "passive"))
      (node (ref "C3") (pin "1") (pinfunction "1_1") (pintype "passive"))
      (node (ref "C30") (pin "1") (pinfunction "1_1") (pintype "passive"))
      (node (ref "C31") (pin "1") (pinfunction "1_1") (pintype "passive"))
      (node (ref "C32") (pin "1") (pinfunction "1_1") (pintype "passive"))
      (node (ref "C33") (pin "-") (pinfunction "-_-") (pintype "passive"))
      (node (ref "C34") (pin "2") (pinfunction "2_2") (pintype "passive"))
      (node (ref "C35") (pin "1") (pinfunction "1_1") (pintype "passive"))
      (node (ref "C36") (pin "2") (pinfunction "2_2") (pintype "passive"))
      (node (ref "C37") (pin "2") (pinfunction "2_2") (pintype "passive"))
      (node (ref "C38") (pin "-") (pinfunction "-_-") (pintype "passive"))
      (node (ref "C39") (pin "-") (pinfunction "-_-") (pintype "passive"))
      (node (ref "C4") (pin "2") (pinfunction "2_2") (pintype "passive"))
      (node (ref "C40") (pin "2") (pinfunction "2_2") (pintype "passive"))
      (node (ref "C41") (pin "1") (pinfunction "1_1") (pintype "passive"))
      (node (ref "C42") (pin "-") (pinfunction "-_-") (pintype "passive"))
      (node (ref "C44") (pin "2") (pinfunction "2_2") (pintype "passive"))
      (node (ref "C45") (pin "1") (pinfunction "1_1") (pintype "passive"))
      (node (ref "C46") (pin "1") (pinfunction "1_1") (pintype "passive"))
      (node (ref "C47") (pin "1") (pinfunction "1_1") (pintype "passive"))
      (node (ref "C48") (pin "1") (pinfunction "1_1") (pintype "passive"))
      (node (ref "C49") (pin "1") (pinfunction "1_1") (pintype "passive"))
      (node (ref "C5") (pin "2") (pinfunction "2_2") (pintype "passive"))
      (node (ref "C50") (pin "1") (pinfunction "1_1") (pintype "passive"))
      (node (ref "C51") (pin "1") (pinfunction "1_1") (pintype "passive"))
      (node (ref "C52") (pin "2") (pinfunction "2_2") (pintype "passive"))
      (node (ref "C53") (pin "2") (pinfunction "2_2") (pintype "passive"))
      (node (ref "C55") (pin "2") (pinfunction "2_2") (pintype "passive"))
      (node (ref "C56") (pin "2") (pinfunction "2_2") (pintype "passive"))
      (node (ref "C57") (pin "1") (pinfunction "1_1") (pintype "passive"))
      (node (ref "C58") (pin "2") (pinfunction "2_2") (pintype "passive"))
      (node (ref "C59") (pin "2") (pinfunction "2_2") (pintype "passive"))
      (node (ref "C6") (pin "2") (pinfunction "2_2") (pintype "passive"))
      (node (ref "C60") (pin "2") (pinfunction "2_2") (pintype "passive"))
      (node (ref "C61") (pin "1") (pinfunction "1_1") (pintype "passive"))
      (node (ref "C62") (pin "1") (pinfunction "1_1") (pintype "passive"))
      (node (ref "C63") (pin "2") (pinfunction "2_2") (pintype "passive"))
      (node (ref "C7") (pin "2") (pinfunction "2_2") (pintype "passive"))
      (node (ref "C74") (pin "2") (pinfunction "2_2") (pintype "passive"))
      (node (ref "C75") (pin "2") (pinfunction "2_2") (pintype "passive"))
      (node (ref "C8") (pin "1") (pinfunction "1_1") (pintype "passive"))
      (node (ref "C9") (pin "1") (pinfunction "1_1") (pintype "passive"))
      (node (ref "D2") (pin "A") (pinfunction "A_A") (pintype "passive"))
      (node (ref "GND1") (pin "0") (pinfunction "GND_0") (pintype "passive"))
      (node (ref "GND10") (pin "0") (pinfunction "GND_0") (pintype "passive"))
      (node (ref "GND11") (pin "0") (pinfunction "GND_0") (pintype "passive"))
      (node (ref "GND12") (pin "0") (pinfunction "GND_0") (pintype "passive"))
      (node (ref "GND13") (pin "0") (pinfunction "GND_0") (pintype "passive"))
      (node (ref "GND14") (pin "0") (pinfunction "GND_0") (pintype "passive"))
      (node (ref "GND15") (pin "0") (pinfunction "GND_0") (pintype "passive"))
      (node (ref "GND16") (pin "0") (pinfunction "GND_0") (pintype "passive"))
      (node (ref "GND17") (pin "0") (pinfunction "GND_0") (pintype "passive"))
      (node (ref "GND18") (pin "0") (pinfunction "GND_0") (pintype "passive"))
      (node (ref "GND19") (pin "0") (pinfunction "GND_0") (pintype "passive"))
      (node (ref "GND2") (pin "0") (pinfunction "GND_0") (pintype "passive"))
      (node (ref "GND20") (pin "0") (pinfunction "GND_0") (pintype "passive"))
      (node (ref "GND21") (pin "0") (pinfunction "GND_0") (pintype "passive"))
      (node (ref "GND22") (pin "0") (pinfunction "GND_0") (pintype "passive"))
      (node (ref "GND23") (pin "0") (pinfunction "GND_0") (pintype "passive"))
      (node (ref "GND24") (pin "0") (pinfunction "GND_0") (pintype "passive"))
      (node (ref "GND25") (pin "0") (pinfunction "GND_0") (pintype "passive"))
      (node (ref "GND26") (pin "0") (pinfunction "GND_0") (pintype "passive"))
      (node (ref "GND27") (pin "0") (pinfunction "GND_0") (pintype "passive"))
      (node (ref "GND28") (pin "0") (pinfunction "GND_0") (pintype "passive"))
      (node (ref "GND29") (pin "0") (pinfunction "GND_0") (pintype "passive"))
      (node (ref "GND3") (pin "0") (pinfunction "GND_0") (pintype "passive"))
      (node (ref "GND30") (pin "0") (pinfunction "GND_0") (pintype "passive"))
      (node (ref "GND31") (pin "0") (pinfunction "GND_0") (pintype "passive"))
      (node (ref "GND32") (pin "0") (pinfunction "GND_0") (pintype "passive"))
      (node (ref "GND33") (pin "0") (pinfunction "GND_0") (pintype "passive"))
      (node (ref "GND34") (pin "0") (pinfunction "GND_0") (pintype "passive"))
      (node (ref "GND35") (pin "0") (pinfunction "GND_0") (pintype "passive"))
      (node (ref "GND36") (pin "0") (pinfunction "GND_0") (pintype "passive"))
      (node (ref "GND4") (pin "0") (pinfunction "GND_0") (pintype "passive"))
      (node (ref "GND6") (pin "0") (pinfunction "GND_0") (pintype "passive"))
      (node (ref "GND7") (pin "0") (pinfunction "GND_0") (pintype "passive"))
      (node (ref "GND8") (pin "0") (pinfunction "GND_0") (pintype "passive"))
      (node (ref "GND9") (pin "0") (pinfunction "GND_0") (pintype "passive"))
      (node (ref "IC1") (pin "3") (pinfunction "GND_3") (pintype "passive"))
      (node (ref "IC1") (pin "6") (pinfunction "GND@1_6") (pintype "passive"))
      (node (ref "IC2") (pin "12") (pinfunction "VSSQ@2_12") (pintype "passive"))
      (node (ref "IC2") (pin "28") (pinfunction "VSS@1_28") (pintype "passive"))
      (node (ref "IC2") (pin "41") (pinfunction "VSS@2_41") (pintype "passive"))
      (node (ref "IC2") (pin "46") (pinfunction "VSSQ@3_46") (pintype "passive"))
      (node (ref "IC2") (pin "52") (pinfunction "VSSQ@4_52") (pintype "passive"))
      (node (ref "IC2") (pin "54") (pinfunction "VSS@3_54") (pintype "passive"))
      (node (ref "IC2") (pin "6") (pinfunction "VSSQ@1_6") (pintype "passive"))
      (node (ref "IC4") (pin "4") (pinfunction "GND_4") (pintype "passive"))
      (node (ref "J4") (pin "13") (pinfunction "13_13") (pintype "passive"))
      (node (ref "J4") (pin "14") (pinfunction "14_14") (pintype "passive"))
      (node (ref "Q2") (pin "2") (pinfunction "S_2") (pintype "passive"))
      (node (ref "R12") (pin "2") (pinfunction "2_2") (pintype "passive"))
      (node (ref "R14") (pin "1") (pinfunction "1_1") (pintype "passive"))
      (node (ref "R15") (pin "2") (pinfunction "2_2") (pintype "passive"))
      (node (ref "R16") (pin "2") (pinfunction "2_2") (pintype "passive"))
      (node (ref "R17") (pin "2") (pinfunction "2_2") (pintype "passive"))
      (node (ref "R22") (pin "2") (pinfunction "2_2") (pintype "passive"))
      (node (ref "R32") (pin "1") (pinfunction "1_1") (pintype "passive"))
      (node (ref "R7") (pin "1") (pinfunction "1_1") (pintype "passive"))
      (node (ref "R8") (pin "1") (pinfunction "1_1") (pintype "passive"))
      (node (ref "R9") (pin "1") (pinfunction "1_1") (pintype "passive"))
      (node (ref "SJ6") (pin "2") (pinfunction "2_2") (pintype "passive"))
      (node (ref "SV1") (pin "10") (pinfunction "10_10") (pintype "passive"))
      (node (ref "SV1") (pin "12") (pinfunction "12_12") (pintype "passive"))
      (node (ref "SV1") (pin "14") (pinfunction "14_14") (pintype "passive"))
      (node (ref "SV1") (pin "4") (pinfunction "4_4") (pintype "passive"))
      (node (ref "SV1") (pin "6") (pinfunction "6_6") (pintype "passive"))
      (node (ref "SV1") (pin "8") (pinfunction "8_8") (pintype "passive"))
      (node (ref "SW1") (pin "3") (pinfunction "3_3") (pintype "passive"))
      (node (ref "SW1") (pin "4") (pinfunction "4_4") (pintype "passive"))
      (node (ref "U$1") (pin "P$1") (pinfunction "GND1_P$1") (pintype "passive"))
      (node (ref "U$1") (pin "P$13") (pinfunction "GND_4_P$13") (pintype "passive"))
      (node (ref "U$1") (pin "P$17") (pinfunction "GND_5_P$17") (pintype "passive"))
      (node (ref "U$1") (pin "P$2") (pinfunction "GND2_P$2") (pintype "passive"))
      (node (ref "U$1") (pin "P$24") (pinfunction "GND_6_P$24") (pintype "passive"))
      (node (ref "U$1") (pin "P$3") (pinfunction "GND3_P$3") (pintype "passive"))
      (node (ref "U$1") (pin "P$30") (pinfunction "GND_7_P$30") (pintype "passive"))
      (node (ref "U$1") (pin "P$37") (pinfunction "GND_8_P$37") (pintype "passive"))
      (node (ref "U$1") (pin "P$41") (pinfunction "CRS/CONFIG1_P$41") (pintype "passive"))
      (node (ref "U$2") (pin "P$4") (pinfunction "GND@1_P$4") (pintype "passive"))
      (node (ref "U1") (pin "7") (pinfunction "GND_7") (pintype "passive"))
      (node (ref "U3") (pin "113") (pinfunction "GND@113_113") (pintype "passive"))
      (node (ref "U3") (pin "133") (pinfunction "GND@133_133") (pintype "passive"))
      (node (ref "U3") (pin "14") (pinfunction "GND@14_14") (pintype "passive"))
      (node (ref "U3") (pin "146") (pinfunction "GND@146_146") (pintype "passive"))
      (node (ref "U3") (pin "153") (pinfunction "GNDPLL@153_153") (pintype "passive"))
      (node (ref "U3") (pin "156") (pinfunction "GNDANA_156") (pintype "passive"))
      (node (ref "U3") (pin "170") (pinfunction "GND@170_170") (pintype "passive"))
      (node (ref "U3") (pin "173") (pinfunction "GND@173_173") (pintype "passive"))
      (node (ref "U3") (pin "188") (pinfunction "GND@188_188") (pintype "passive"))
      (node (ref "U3") (pin "200") (pinfunction "GND@200_200") (pintype "passive"))
      (node (ref "U3") (pin "204") (pinfunction "GND@204_204") (pintype "passive"))
      (node (ref "U3") (pin "25") (pinfunction "GND@25_25") (pintype "passive"))
      (node (ref "U3") (pin "33") (pinfunction "GND@33_33") (pintype "passive"))
      (node (ref "U3") (pin "39") (pinfunction "GND@39_39") (pintype "passive"))
      (node (ref "U3") (pin "44") (pinfunction "GNDBU_44") (pintype "passive"))
      (node (ref "U3") (pin "53") (pinfunction "GND@53_53") (pintype "passive"))
      (node (ref "U3") (pin "6") (pinfunction "GND@6_6") (pintype "passive"))
      (node (ref "U3") (pin "66") (pinfunction "GND@66_66") (pintype "passive"))
      (node (ref "U3") (pin "78") (pinfunction "GND@78_78") (pintype "passive"))
      (node (ref "U3") (pin "91") (pinfunction "GND@91_91") (pintype "passive"))
      (node (ref "USD") (pin "6") (pinfunction "VSS_6") (pintype "passive"))
      (node (ref "V7") (pin "0") (pinfunction "GND_0") (pintype "passive"))
      (node (ref "V8") (pin "0") (pinfunction "GND_0") (pintype "passive"))
      (node (ref "VR1") (pin "2") (pinfunction "GND_2") (pintype "passive"))
      (node (ref "VREG1") (pin "1") (pinfunction "GND_1") (pintype "passive"))
      (node (ref "WAKE") (pin "1") (pinfunction "1_1") (pintype "passive"))
      (node (ref "WAKE") (pin "2") (pinfunction "2_2") (pintype "passive"))
      (node (ref "X1") (pin "GND") (pinfunction "GND_GND") (pintype "passive"))
      (node (ref "X2") (pin "GND") (pinfunction "GND_GND") (pintype "passive"))
      (node (ref "X4") (pin "7") (pinfunction "KL_7") (pintype "passive"))
      (node (ref "X4") (pin "8") (pinfunction "KL_8") (pintype "passive"))
    )
    (net (code "6") (name "/LED_A") (class "Default")
      (node (ref "U$1") (pin "P$43") (pinfunction "LED1/SPEED_P$43") (pintype "passive"))
    )
    (net (code "7") (name "/LED_B") (class "Default")
      (node (ref "U$1") (pin "P$42") (pinfunction "LED0/NWAYEN_P$42") (pintype "passive"))
    )
    (net (code "9") (name "/NRST") (class "Default")
      (node (ref "U$1") (pin "P$47") (pinfunction "RST#_P$47") (pintype "passive"))
      (node (ref "U1") (pin "3") (pinfunction "!RST!_3") (pintype "passive"))
      (node (ref "X4") (pin "4") (pinfunction "KL_4") (pintype "passive"))
    )
    (net (code "10") (name "/RD+") (class "Default")
      (node (ref "R24") (pin "1") (pinfunction "1_1") (pintype "passive"))
      (node (ref "U$1") (pin "P$10") (pinfunction "RX+_P$10") (pintype "passive"))
    )
    (net (code "11") (name "/RD-") (class "Default")
      (node (ref "J4") (pin "6") (pinfunction "6_6") (pintype "passive"))
      (node (ref "R10") (pin "1") (pinfunction "1_1") (pintype "passive"))
    )
    (net (code "12") (name "/SHDN") (class "Default")
      (node (ref "R30") (pin "1") (pinfunction "1_1") (pintype "passive"))
      (node (ref "U3") (pin "49") (pinfunction "SHDN_49") (pintype "passive"))
    )
    (net (code "13") (name "/TD+") (class "Default")
      (node (ref "J4") (pin "1") (pinfunction "1_1") (pintype "passive"))
      (node (ref "R28") (pin "1") (pinfunction "1_1") (pintype "passive"))
      (node (ref "U$1") (pin "P$12") (pinfunction "TX+_P$12") (pintype "passive"))
    )
    (net (code "14") (name "/TD-") (class "Default")
      (node (ref "J4") (pin "2") (pinfunction "2_2") (pintype "passive"))
      (node (ref "R26") (pin "1") (pinfunction "1_1") (pintype "passive"))
      (node (ref "U$1") (pin "P$11") (pinfunction "TX-_P$11") (pintype "passive"))
    )
    (net (code "15") (name "/TWCK") (class "Default")
      (node (ref "U3") (pin "1") (pinfunction "PA24/TWCK/ETX3_1") (pintype "passive"))
      (node (ref "X4") (pin "30") (pinfunction "KL_30") (pintype "passive"))
    )
    (net (code "16") (name "/TWD") (class "Default")
      (node (ref "U3") (pin "208") (pinfunction "PA23/TWD/ETX2_208") (pintype "passive"))
      (node (ref "X4") (pin "29") (pinfunction "KL_29") (pintype "passive"))
    )
    (net (code "17") (name "/VDDBU") (class "Default")
      (node (ref "X4") (pin "6") (pinfunction "KL_6") (pintype "passive"))
    )
    (net (code "18") (name "Net-(BATT1-PadV2)") (class "Default")
      (node (ref "BATT1") (pin "V2") (pinfunction "V2_V2") (pintype "passive"))
      (node (ref "R23") (pin "1") (pinfunction "1_1") (pintype "passive"))
    )
    (net (code "19") (name "Net-(C3-Pad2)") (class "Default")
      (node (ref "C3") (pin "2") (pinfunction "2_2") (pintype "passive"))
      (node (ref "R11") (pin "1") (pinfunction "1_1") (pintype "passive"))
      (node (ref "X1") (pin "VBUS") (pinfunction "VBUS_VBUS") (pintype "passive"))
    )
    (net (code "20") (name "Net-(C4-Pad1)") (class "Default")
      (node (ref "C4") (pin "1") (pinfunction "1_1") (pintype "passive"))
      (node (ref "R3") (pin "1") (pinfunction "1_1") (pintype "passive"))
      (node (ref "R7") (pin "2") (pinfunction "2_2") (pintype "passive"))
      (node (ref "X2") (pin "D-") (pinfunction "D-_D-") (pintype "passive"))
    )
    (net (code "21") (name "Net-(C5-Pad1)") (class "Default")
      (node (ref "C5") (pin "1") (pinfunction "1_1") (pintype "passive"))
      (node (ref "R4") (pin "1") (pinfunction "1_1") (pintype "passive"))
      (node (ref "R8") (pin "2") (pinfunction "2_2") (pintype "passive"))
      (node (ref "X2") (pin "D+") (pinfunction "D+_D+") (pintype "passive"))
    )
    (net (code "22") (name "Net-(C31-Pad2)") (class "Default")
      (node (ref "C31") (pin "2") (pinfunction "2_2") (pintype "passive"))
      (node (ref "R20") (pin "2") (pinfunction "2_2") (pintype "passive"))
    )
    (net (code "23") (name "Net-(C75-Pad1)") (class "Default")
      (node (ref "C75") (pin "1") (pinfunction "1_1") (pintype "passive"))
      (node (ref "R10") (pin "2") (pinfunction "2_2") (pintype "passive"))
      (node (ref "R24") (pin "2") (pinfunction "2_2") (pintype "passive"))
    )
    (net (code "24") (name "Net-(F1-Pad1)") (class "Default")
      (node (ref "F1") (pin "1") (pinfunction "1_1") (pintype "passive"))
      (node (ref "X2") (pin "VBUS") (pinfunction "VBUS_VBUS") (pintype "passive"))
    )
    (net (code "25") (name "Net-(IC1-EN)") (class "Default")
      (node (ref "IC1") (pin "5") (pinfunction "EN_5") (pintype "passive"))
      (node (ref "IC4") (pin "7") (pinfunction "SHDN#_7") (pintype "passive"))
      (node (ref "Q2") (pin "3") (pinfunction "D_3") (pintype "passive"))
      (node (ref "R29") (pin "1") (pinfunction "1_1") (pintype "passive"))
    )
    (net (code "26") (name "Net-(IC1-IN)") (class "Default")
      (node (ref "C33") (pin "+") (pinfunction "+_+") (pintype "passive"))
      (node (ref "D1") (pin "C") (pinfunction "C_C") (pintype "passive"))
      (node (ref "IC1") (pin "1") (pinfunction "IN_1") (pintype "passive"))
      (node (ref "R29") (pin "2") (pinfunction "2_2") (pintype "passive"))
      (node (ref "VREG1") (pin "3") (pinfunction "VIN_3") (pintype "passive"))
    )
    (net (code "27") (name "Net-(IC1-OUT)") (class "Default")
      (node (ref "D2") (pin "C") (pinfunction "C_C") (pintype "passive"))
      (node (ref "IC1") (pin "2") (pinfunction "OUT_2") (pintype "passive"))
      (node (ref "U$3") (pin "1") (pinfunction "1_1") (pintype "passive"))
    )
    (net (code "28") (name "Net-(IC2A-!CAS)") (class "Default")
      (node (ref "IC2") (pin "17") (pinfunction "!CAS_17") (pintype "passive"))
      (node (ref "U3") (pin "104") (pinfunction "!CAS_104") (pintype "passive"))
    )
    (net (code "29") (name "Net-(IC2A-!RAS)") (class "Default")
      (node (ref "IC2") (pin "18") (pinfunction "!RAS_18") (pintype "passive"))
      (node (ref "U3") (pin "105") (pinfunction "!RAS_105") (pintype "passive"))
    )
    (net (code "30") (name "Net-(IC2A-!WE)") (class "Default")
      (node (ref "IC2") (pin "16") (pinfunction "!WE_16") (pintype "passive"))
      (node (ref "U3") (pin "116") (pinfunction "!SDWE_116") (pintype "passive"))
    )
    (net (code "31") (name "Net-(IC2A-A0)") (class "Default")
      (node (ref "IC2") (pin "23") (pinfunction "A0_23") (pintype "passive"))
      (node (ref "U3") (pin "98") (pinfunction "NWR2/NBS2/A1_98") (pintype "passive"))
    )
    (net (code "32") (name "Net-(IC2A-A1)") (class "Default")
      (node (ref "IC2") (pin "24") (pinfunction "A1_24") (pintype "passive"))
      (node (ref "U3") (pin "97") (pinfunction "A2_97") (pintype "passive"))
    )
    (net (code "33") (name "Net-(IC2A-A2)") (class "Default")
      (node (ref "IC2") (pin "25") (pinfunction "A2_25") (pintype "passive"))
      (node (ref "U3") (pin "96") (pinfunction "A3_96") (pintype "passive"))
    )
    (net (code "34") (name "Net-(IC2A-A3)") (class "Default")
      (node (ref "IC2") (pin "26") (pinfunction "A3_26") (pintype "passive"))
      (node (ref "U3") (pin "95") (pinfunction "A4_95") (pintype "passive"))
    )
    (net (code "35") (name "Net-(IC2A-A4)") (class "Default")
      (node (ref "IC2") (pin "29") (pinfunction "A4_29") (pintype "passive"))
      (node (ref "U3") (pin "94") (pinfunction "A5_94") (pintype "passive"))
    )
    (net (code "36") (name "Net-(IC2A-A5)") (class "Default")
      (node (ref "IC2") (pin "30") (pinfunction "A5_30") (pintype "passive"))
      (node (ref "U3") (pin "93") (pinfunction "A6_93") (pintype "passive"))
    )
    (net (code "37") (name "Net-(IC2A-A6)") (class "Default")
      (node (ref "IC2") (pin "31") (pinfunction "A6_31") (pintype "passive"))
      (node (ref "U3") (pin "92") (pinfunction "A7_92") (pintype "passive"))
    )
    (net (code "38") (name "Net-(IC2A-A7)") (class "Default")
      (node (ref "IC2") (pin "32") (pinfunction "A7_32") (pintype "passive"))
      (node (ref "U3") (pin "89") (pinfunction "A8_89") (pintype "passive"))
    )
    (net (code "39") (name "Net-(IC2A-A8)") (class "Default")
      (node (ref "IC2") (pin "33") (pinfunction "A8_33") (pintype "passive"))
      (node (ref "U3") (pin "88") (pinfunction "A9_88") (pintype "passive"))
    )
    (net (code "40") (name "Net-(IC2A-A9)") (class "Default")
      (node (ref "IC2") (pin "34") (pinfunction "A9_34") (pintype "passive"))
      (node (ref "U3") (pin "100") (pinfunction "SDA10_100") (pintype "passive"))
    )
    (net (code "41") (name "Net-(IC2A-A10)") (class "Default")
      (node (ref "IC2") (pin "22") (pinfunction "A10_22") (pintype "passive"))
      (node (ref "U3") (pin "86") (pinfunction "A11_86") (pintype "passive"))
    )
    (net (code "42") (name "Net-(IC2A-A11)") (class "Default")
      (node (ref "IC2") (pin "35") (pinfunction "A11_35") (pintype "passive"))
      (node (ref "U3") (pin "85") (pinfunction "A12_85") (pintype "passive"))
    )
    (net (code "43") (name "Net-(IC2A-A12)") (class "Default")
      (node (ref "IC2") (pin "36") (pinfunction "A12_36") (pintype "passive"))
      (node (ref "R31") (pin "1") (pinfunction "1_1") (pintype "passive"))
    )
    (net (code "44") (name "Net-(IC2A-BA0)") (class "Default")
      (node (ref "IC2") (pin "20") (pinfunction "BA0_20") (pintype "passive"))
      (node (ref "U3") (pin "81") (pinfunction "BA0/A16_81") (pintype "passive"))
    )
    (net (code "45") (name "Net-(IC2A-BA1)") (class "Default")
      (node (ref "IC2") (pin "21") (pinfunction "BA1_21") (pintype "passive"))
      (node (ref "U3") (pin "80") (pinfunction "BA1/A17_80") (pintype "passive"))
    )
    (net (code "46") (name "Net-(IC2A-CKE)") (class "Default")
      (node (ref "IC2") (pin "37") (pinfunction "CKE_37") (pintype "passive"))
      (node (ref "U3") (pin "117") (pinfunction "SDCKE_117") (pintype "passive"))
    )
    (net (code "47") (name "Net-(IC2A-CLK)") (class "Default")
      (node (ref "IC2") (pin "38") (pinfunction "CLK_38") (pintype "passive"))
      (node (ref "U3") (pin "115") (pinfunction "SDCK_115") (pintype "passive"))
    )
    (net (code "48") (name "Net-(IC2A-CS)") (class "Default")
      (node (ref "IC2") (pin "19") (pinfunction "CS_19") (pintype "passive"))
      (node (ref "R6") (pin "2") (pinfunction "2_2") (pintype "passive"))
      (node (ref "U3") (pin "103") (pinfunction "SDCS/NCS1_103") (pintype "passive"))
    )
    (net (code "49") (name "Net-(IC2A-DQMH)") (class "Default")
      (node (ref "IC2") (pin "39") (pinfunction "DQMH_39") (pintype "passive"))
      (node (ref "U3") (pin "102") (pinfunction "CFIOR/NBS1/NWR1_102") (pintype "passive"))
    )
    (net (code "50") (name "Net-(IC2A-DQML)") (class "Default")
      (node (ref "IC2") (pin "15") (pinfunction "DQML_15") (pintype "passive"))
      (node (ref "U3") (pin "99") (pinfunction "NBS0/A0_99") (pintype "passive"))
    )
    (net (code "51") (name "Net-(IC4-C+)") (class "Default")
      (node (ref "C43") (pin "2") (pinfunction "2_2") (pintype "passive"))
      (node (ref "IC4") (pin "6") (pinfunction "C+_6") (pintype "passive"))
    )
    (net (code "52") (name "Net-(IC4-C-)") (class "Default")
      (node (ref "C43") (pin "1") (pinfunction "1_1") (pintype "passive"))
      (node (ref "IC4") (pin "5") (pinfunction "C-_5") (pintype "passive"))
    )
    (net (code "53") (name "Net-(IC4-FB)") (class "Default")
      (node (ref "IC4") (pin "8") (pinfunction "FB_8") (pintype "passive"))
      (node (ref "R32") (pin "2") (pinfunction "2_2") (pintype "passive"))
      (node (ref "R33") (pin "2") (pinfunction "2_2") (pintype "passive"))
    )
    (net (code "54") (name "Net-(IC4-PGOOD)") (class "Default")
      (node (ref "IC4") (pin "1") (pinfunction "PGOOD_1") (pintype "passive"))
      (node (ref "R34") (pin "1") (pinfunction "1_1") (pintype "passive"))
    )
    (net (code "55") (name "Net-(J4-Pad4)") (class "Default")
      (node (ref "J4") (pin "4") (pinfunction "4_4") (pintype "passive"))
      (node (ref "J4") (pin "5") (pinfunction "5_5") (pintype "passive"))
    )
    (net (code "56") (name "Net-(J4-Pad10)") (class "Default")
      (node (ref "J4") (pin "10") (pinfunction "10_10") (pintype "passive"))
      (node (ref "R4A") (pin "2") (pinfunction "2_2") (pintype "passive"))
    )
    (net (code "57") (name "Net-(J4-Pad11)") (class "Default")
      (node (ref "J4") (pin "11") (pinfunction "11_11") (pintype "passive"))
      (node (ref "R5A") (pin "2") (pinfunction "2_2") (pintype "passive"))
    )
    (net (code "58") (name "Net-(L2-1)") (class "Default")
      (node (ref "C12") (pin "2") (pinfunction "2_2") (pintype "passive"))
      (node (ref "C26") (pin "2") (pinfunction "2_2") (pintype "passive"))
      (node (ref "L2") (pin "2") (pinfunction "1_2") (pintype "passive"))
      (node (ref "U$1") (pin "P$7") (pinfunction "VDDA_3.3_1_P$7") (pintype "passive"))
      (node (ref "U$1") (pin "P$8") (pinfunction "VDDA_3.3_2_P$8") (pintype "passive"))
    )
    (net (code "59") (name "Net-(L3-1)") (class "Default")
      (node (ref "C36") (pin "1") (pinfunction "1_1") (pintype "passive"))
      (node (ref "C52") (pin "1") (pinfunction "1_1") (pintype "passive"))
      (node (ref "L3") (pin "2") (pinfunction "1_2") (pintype "passive"))
      (node (ref "L4") (pin "2") (pinfunction "1_2") (pintype "passive"))
      (node (ref "U$1") (pin "P$6") (pinfunction "V1.8_OUT_P$6") (pintype "passive"))
    )
    (net (code "60") (name "Net-(L3-2)") (class "Default")
      (node (ref "C55") (pin "1") (pinfunction "1_1") (pintype "passive"))
      (node (ref "C56") (pin "1") (pinfunction "1_1") (pintype "passive"))
      (node (ref "L3") (pin "1") (pinfunction "2_1") (pintype "passive"))
      (node (ref "U$1") (pin "P$4") (pinfunction "VDDA_1.8_1_P$4") (pintype "passive"))
      (node (ref "U$1") (pin "P$5") (pinfunction "VDDA_1.8_2_P$5") (pintype "passive"))
    )
    (net (code "61") (name "Net-(L4-2)") (class "Default")
      (node (ref "C57") (pin "2") (pinfunction "2_2") (pintype "passive"))
      (node (ref "L4") (pin "1") (pinfunction "2_1") (pintype "passive"))
      (node (ref "U$1") (pin "P$31") (pinfunction "VDD_1.8_3_P$31") (pintype "passive"))
    )
    (net (code "62") (name "Net-(LED1-PadC)") (class "Default")
      (node (ref "LED1") (pin "C") (pinfunction "C_C") (pintype "passive"))
      (node (ref "R16") (pin "1") (pinfunction "1_1") (pintype "passive"))
    )
    (net (code "63") (name "Net-(LED2-PadC)") (class "Default")
      (node (ref "LED2") (pin "C") (pinfunction "C_C") (pintype "passive"))
      (node (ref "R17") (pin "1") (pinfunction "1_1") (pintype "passive"))
    )
    (net (code "64") (name "Net-(LED3-PadC)") (class "Default")
      (node (ref "LED3") (pin "C") (pinfunction "C_C") (pintype "passive"))
      (node (ref "R22") (pin "1") (pinfunction "1_1") (pintype "passive"))
    )
    (net (code "65") (name "Net-(LINK/ACT-PadC)") (class "Default")
      (node (ref "LINK/ACT") (pin "C") (pinfunction "C_C") (pintype "passive"))
      (node (ref "R35") (pin "2") (pinfunction "2_2") (pintype "passive"))
    )
    (net (code "66") (name "Net-(Q2-G)") (class "Default")
      (node (ref "C32") (pin "2") (pinfunction "2_2") (pintype "passive"))
      (node (ref "Q2") (pin "1") (pinfunction "G_1") (pintype "passive"))
      (node (ref "R30") (pin "2") (pinfunction "2_2") (pintype "passive"))
    )
    (net (code "67") (name "Net-(R1-Pad1)") (class "Default")
      (node (ref "R1") (pin "1") (pinfunction "1_1") (pintype "passive"))
      (node (ref "X1") (pin "D+") (pinfunction "D+_D+") (pintype "passive"))
    )
    (net (code "68") (name "Net-(R2-Pad1)") (class "Default")
      (node (ref "R2") (pin "1") (pinfunction "1_1") (pintype "passive"))
      (node (ref "X1") (pin "D-") (pinfunction "D-_D-") (pintype "passive"))
    )
    (net (code "69") (name "Net-(R36-Pad2)") (class "Default")
      (node (ref "R36") (pin "2") (pinfunction "2_2") (pintype "passive"))
      (node (ref "SPEED") (pin "C") (pinfunction "C_C") (pintype "passive"))
    )
    (net (code "70") (name "Net-(RN2B-1)") (class "Default")
      (node (ref "RN2") (pin "2") (pinfunction "1_2") (pintype "passive"))
      (node (ref "SV1") (pin "7") (pinfunction "7_7") (pintype "passive"))
      (node (ref "U3") (pin "31") (pinfunction "TMS_31") (pintype "passive"))
    )
    (net (code "71") (name "Net-(RN2C-1)") (class "Default")
      (node (ref "RN2") (pin "3") (pinfunction "1_3") (pintype "passive"))
      (node (ref "SV1") (pin "5") (pinfunction "5_5") (pintype "passive"))
      (node (ref "U3") (pin "30") (pinfunction "TDI_30") (pintype "passive"))
    )
    (net (code "72") (name "Net-(RN2D-1)") (class "Default")
      (node (ref "RN2") (pin "4") (pinfunction "1_4") (pintype "passive"))
      (node (ref "SV1") (pin "3") (pinfunction "3_3") (pintype "passive"))
      (node (ref "U3") (pin "35") (pinfunction "NTRST_35") (pintype "passive"))
    )
    (net (code "73") (name "Net-(U$1-REXT)") (class "Default")
      (node (ref "C61") (pin "2") (pinfunction "2_2") (pintype "passive"))
      (node (ref "R15") (pin "1") (pinfunction "1_1") (pintype "passive"))
      (node (ref "U$1") (pin "P$16") (pinfunction "REXT_P$16") (pintype "passive"))
    )
    (net (code "74") (name "Net-(U$1-RXD0{slash}RXD[0]{slash}RX_DUPLEX)") (class "Default")
      (node (ref "U$1") (pin "P$23") (pinfunction "RXD0/RXD[0]/RX_DUPLEX_P$23") (pintype "passive"))
      (node (ref "U3") (pin "195") (pinfunction "PA14/ERX0_195") (pintype "passive"))
    )
    (net (code "75") (name "Net-(U$1-RXD1{slash}RXD[1]{slash}PHYAD02)") (class "Default")
      (node (ref "U$1") (pin "P$22") (pinfunction "RXD1/RXD[1]/PHYAD02_P$22") (pintype "passive"))
      (node (ref "U3") (pin "196") (pinfunction "PA15/ERX1_196") (pintype "passive"))
    )
    (net (code "76") (name "Net-(U$1-RXDV{slash}CRSDV{slash}CONFIG2)") (class "Default")
      (node (ref "R9") (pin "2") (pinfunction "2_2") (pintype "passive"))
      (node (ref "U$1") (pin "P$27") (pinfunction "RXDV/CRSDV/CONFIG2_P$27") (pintype "passive"))
      (node (ref "U3") (pin "198") (pinfunction "PA17/ERXDV_198") (pintype "passive"))
    )
    (net (code "77") (name "Net-(U$1-RXER{slash}RX_ER{slash}ISO)") (class "Default")
      (node (ref "U$1") (pin "P$29") (pinfunction "RXER/RX_ER/ISO_P$29") (pintype "passive"))
      (node (ref "U3") (pin "201") (pinfunction "PA18/ERXER_201") (pintype "passive"))
    )
    (net (code "78") (name "Net-(U$1-TXD0{slash}TXD[0]{slash}TX)") (class "Default")
      (node (ref "U$1") (pin "P$35") (pinfunction "TXD0/TXD[0]/TX_P$35") (pintype "passive"))
      (node (ref "U3") (pin "193") (pinfunction "PA12/ETX0_193") (pintype "passive"))
    )
    (net (code "79") (name "Net-(U$1-TXD1{slash}TXD[1]{slash}SYNC)") (class "Default")
      (node (ref "U$1") (pin "P$36") (pinfunction "TXD1/TXD[1]/SYNC_P$36") (pintype "passive"))
      (node (ref "U3") (pin "194") (pinfunction "PA13/ETX1_194") (pintype "passive"))
    )
    (net (code "80") (name "Net-(U$1-TXEN{slash}TX_EN)") (class "Default")
      (node (ref "U$1") (pin "P$34") (pinfunction "TXEN/TX_EN_P$34") (pintype "passive"))
      (node (ref "U3") (pin "197") (pinfunction "PA16/ETXEN_197") (pintype "passive"))
    )
    (net (code "81") (name "Net-(U$1-XI{slash}REFCLK{slash}CLOCK)") (class "Default")
      (node (ref "U$1") (pin "P$15") (pinfunction "XI/REFCLK/CLOCK_P$15") (pintype "passive"))
      (node (ref "U3") (pin "202") (pinfunction "PA19/ETXCK_202") (pintype "passive"))
    )
    (net (code "82") (name "Net-(U$2-PWR)") (class "Default")
      (node (ref "D1") (pin "A") (pinfunction "A_A") (pintype "passive"))
      (node (ref "U$2") (pin "VIN0") (pinfunction "PWR_VIN0") (pintype "passive"))
    )
    (net (code "83") (name "Net-(U1-!CS!)") (class "Default")
      (node (ref "R5") (pin "1") (pinfunction "1_1") (pintype "passive"))
      (node (ref "U1") (pin "4") (pinfunction "!CS!_4") (pintype "passive"))
      (node (ref "U3") (pin "182") (pinfunction "PA3/SPI0_NPCS0/MCDB3_182") (pintype "passive"))
    )
    (net (code "84") (name "Net-(U1-!WP!)") (class "Default")
      (node (ref "SJ6") (pin "1") (pinfunction "1_1") (pintype "passive"))
      (node (ref "U1") (pin "5") (pinfunction "!WP!_5") (pintype "passive"))
    )
    (net (code "85") (name "Net-(U1-SCK)") (class "Default")
      (node (ref "U1") (pin "2") (pinfunction "SCK_2") (pintype "passive"))
      (node (ref "U3") (pin "181") (pinfunction "PA2/SPI0_SPCK_181") (pintype "passive"))
    )
    (net (code "86") (name "Net-(U1-SI)") (class "Default")
      (node (ref "U1") (pin "1") (pinfunction "SI_1") (pintype "passive"))
      (node (ref "U3") (pin "180") (pinfunction "PA1/SPI0_MOSI/MCCDB_180") (pintype "passive"))
    )
    (net (code "87") (name "Net-(U1-SO)") (class "Default")
      (node (ref "U1") (pin "8") (pinfunction "SO_8") (pintype "passive"))
      (node (ref "U3") (pin "179") (pinfunction "PA0/SPI0_MISO/MCDB0_179") (pintype "passive"))
    )
    (net (code "88") (name "Net-(U3-A13)") (class "Default")
      (node (ref "R31") (pin "2") (pinfunction "2_2") (pintype "passive"))
      (node (ref "U3") (pin "84") (pinfunction "A13_84") (pintype "passive"))
    )
    (net (code "89") (name "Net-(U3-BMS)") (class "Default")
      (node (ref "R25") (pin "2") (pinfunction "2_2") (pintype "passive"))
      (node (ref "U3") (pin "40") (pinfunction "BMS_40") (pintype "passive"))
    )
    (net (code "90") (name "Net-(U3-D14)") (class "Default")
      (node (ref "U3") (pin "125") (pinfunction "D14_125") (pintype "passive"))
      (node (ref "U3") (pin "126") (pinfunction "D15_126") (pintype "passive"))
    )
    (net (code "91") (name "Net-(U3-D29{slash}PC29)") (class "Default")
      (node (ref "LED3") (pin "A") (pinfunction "A_A") (pintype "passive"))
      (node (ref "U3") (pin "143") (pinfunction "D29/PC29_143") (pintype "passive"))
    )
    (net (code "92") (name "Net-(U3-D30{slash}PC30)") (class "Default")
      (node (ref "LED2") (pin "A") (pinfunction "A_A") (pintype "passive"))
      (node (ref "U3") (pin "144") (pinfunction "D30/PC30_144") (pintype "passive"))
    )
    (net (code "93") (name "Net-(U3-D31{slash}PC31)") (class "Default")
      (node (ref "LED1") (pin "A") (pinfunction "A_A") (pintype "passive"))
      (node (ref "U3") (pin "145") (pinfunction "D31/PC31_145") (pintype "passive"))
    )
    (net (code "94") (name "Net-(U3-DDM)") (class "Default")
      (node (ref "C1") (pin "2") (pinfunction "2_2") (pintype "passive"))
      (node (ref "R2") (pin "2") (pinfunction "2_2") (pintype "passive"))
      (node (ref "U3") (pin "54") (pinfunction "DDM_54") (pintype "passive"))
    )
    (net (code "95") (name "Net-(U3-DDP)") (class "Default")
      (node (ref "C2") (pin "2") (pinfunction "2_2") (pintype "passive"))
      (node (ref "R1") (pin "2") (pinfunction "2_2") (pintype "passive"))
      (node (ref "U3") (pin "55") (pinfunction "DDP_55") (pintype "passive"))
    )
    (net (code "96") (name "Net-(U3-DRXD{slash}PB14)") (class "Default")
      (node (ref "U3") (pin "21") (pinfunction "DRXD/PB14_21") (pintype "passive"))
      (node (ref "X4") (pin "5") (pinfunction "KL_5") (pintype "passive"))
    )
    (net (code "97") (name "Net-(U3-DTXD{slash}PB15)") (class "Default")
      (node (ref "U3") (pin "22") (pinfunction "DTXD/PB15_22") (pintype "passive"))
      (node (ref "X4") (pin "3") (pinfunction "KL_3") (pintype "passive"))
    )
    (net (code "98") (name "Net-(U3-GNDPLL@151)") (class "Default")
      (node (ref "C29") (pin "2") (pinfunction "2_2") (pintype "passive"))
      (node (ref "U3") (pin "151") (pinfunction "GNDPLL@151_151") (pintype "passive"))
    )
    (net (code "99") (name "Net-(U3-HDMA)") (class "Default")
      (node (ref "R3") (pin "2") (pinfunction "2_2") (pintype "passive"))
      (node (ref "U3") (pin "50") (pinfunction "HDMA_50") (pintype "passive"))
    )
    (net (code "100") (name "Net-(U3-HDPA)") (class "Default")
      (node (ref "R4") (pin "2") (pinfunction "2_2") (pintype "passive"))
      (node (ref "U3") (pin "51") (pinfunction "HDPA_51") (pintype "passive"))
    )
    (net (code "101") (name "Net-(U3-IRQ1{slash}NWAIT{slash}PC15)") (class "Default")
      (node (ref "U3") (pin "127") (pinfunction "IRQ1/NWAIT/PC15_127") (pintype "passive"))
      (node (ref "X4") (pin "12") (pinfunction "KL_12") (pintype "passive"))
    )
    (net (code "102") (name "Net-(U3-IRQ2{slash}NCS3_NANDCS{slash}PC14)") (class "Default")
      (node (ref "U3") (pin "59") (pinfunction "IRQ2/NCS3_NANDCS/PC14_59") (pintype "passive"))
      (node (ref "X4") (pin "16") (pinfunction "KL_16") (pintype "passive"))
    )
    (net (code "103") (name "Net-(U3-JTAGSEL)") (class "Default")
      (node (ref "SJ3") (pin "2") (pinfunction "2_2") (pintype "passive"))
      (node (ref "U3") (pin "43") (pinfunction "JTAGSEL_43") (pintype "passive"))
    )
    (net (code "104") (name "Net-(U3-NRST)") (class "Default")
      (node (ref "C34") (pin "1") (pinfunction "1_1") (pintype "passive"))
      (node (ref "R27") (pin "2") (pinfunction "2_2") (pintype "passive"))
      (node (ref "SW1") (pin "1") (pinfunction "1_1") (pintype "passive"))
      (node (ref "SW1") (pin "2") (pinfunction "2_2") (pintype "passive"))
      (node (ref "U3") (pin "36") (pinfunction "NRST_36") (pintype "passive"))
    )
    (net (code "105") (name "Net-(U3-OSCSEL)") (class "Default")
      (node (ref "R19") (pin "1") (pinfunction "1_1") (pintype "passive"))
      (node (ref "U3") (pin "41") (pinfunction "OSCSEL_41") (pintype "passive"))
    )
    (net (code "106") (name "Net-(U3-PA6{slash}MCDA0)") (class "Default")
      (node (ref "U3") (pin "185") (pinfunction "PA6/MCDA0_185") (pintype "passive"))
      (node (ref "USD") (pin "7") (pinfunction "DO_7") (pintype "passive"))
    )
    (net (code "107") (name "Net-(U3-PA7{slash}MCCDA)") (class "Default")
      (node (ref "U3") (pin "186") (pinfunction "PA7/MCCDA_186") (pintype "passive"))
      (node (ref "USD") (pin "3") (pinfunction "DI_3") (pintype "passive"))
    )
    (net (code "108") (name "Net-(U3-PA8{slash}MCCK)") (class "Default")
      (node (ref "R13") (pin "1") (pinfunction "1_1") (pintype "passive"))
      (node (ref "U3") (pin "189") (pinfunction "PA8/MCCK_189") (pintype "passive"))
      (node (ref "USD") (pin "5") (pinfunction "SCLK_5") (pintype "passive"))
    )
    (net (code "109") (name "Net-(U3-PA9{slash}MCDA1)") (class "Default")
      (node (ref "U3") (pin "190") (pinfunction "PA9/MCDA1_190") (pintype "passive"))
      (node (ref "USD") (pin "8") (pinfunction "DATA1_8") (pintype "passive"))
    )
    (net (code "110") (name "Net-(U3-PA10{slash}MCDA2{slash}ETX2)") (class "Default")
      (node (ref "U3") (pin "191") (pinfunction "PA10/MCDA2/ETX2_191") (pintype "passive"))
      (node (ref "USD") (pin "1") (pinfunction "DATA2_1") (pintype "passive"))
    )
    (net (code "111") (name "Net-(U3-PA11{slash}MCDA3{slash}ETX3)") (class "Default")
      (node (ref "U3") (pin "192") (pinfunction "PA11/MCDA3/ETX3_192") (pintype "passive"))
      (node (ref "USD") (pin "2") (pinfunction "CS_2") (pintype "passive"))
    )
    (net (code "112") (name "Net-(U3-PA26{slash}TIOA0{slash}ERX3)") (class "Default")
      (node (ref "R11") (pin "2") (pinfunction "2_2") (pintype "passive"))
      (node (ref "R12") (pin "1") (pinfunction "1_1") (pintype "passive"))
      (node (ref "U3") (pin "3") (pinfunction "PA26/TIOA0/ERX3_3") (pintype "passive"))
    )
    (net (code "113") (name "Net-(U3-PCK0{slash}AD1{slash}PC1)") (class "Default")
      (node (ref "U3") (pin "159") (pinfunction "PCK0/AD1/PC1_159") (pintype "passive"))
      (node (ref "X4") (pin "9") (pinfunction "KL_9") (pintype "passive"))
    )
    (net (code "114") (name "Net-(U3-PLLRCA)") (class "Default")
      (node (ref "C30") (pin "2") (pinfunction "2_2") (pintype "passive"))
      (node (ref "R20") (pin "1") (pinfunction "1_1") (pintype "passive"))
      (node (ref "U3") (pin "154") (pinfunction "PLLRCA_154") (pintype "passive"))
    )
    (net (code "115") (name "Net-(U3-RTCK)") (class "Default")
      (node (ref "SV1") (pin "11") (pinfunction "11_11") (pintype "passive"))
      (node (ref "U3") (pin "37") (pinfunction "RTCK_37") (pintype "passive"))
    )
    (net (code "116") (name "Net-(U3-RXD0{slash}PB5)") (class "Default")
      (node (ref "U3") (pin "16") (pinfunction "RXD0/PB5_16") (pintype "passive"))
      (node (ref "X4") (pin "23") (pinfunction "KL_23") (pintype "passive"))
    )
    (net (code "117") (name "Net-(U3-RXD2{slash}PB9)") (class "Default")
      (node (ref "U3") (pin "20") (pinfunction "RXD2/PB9_20") (pintype "passive"))
      (node (ref "X4") (pin "19") (pinfunction "KL_19") (pintype "passive"))
    )
    (net (code "118") (name "Net-(U3-SCK3{slash}AD0{slash}PC0)") (class "Default")
      (node (ref "U3") (pin "158") (pinfunction "SCK3/AD0/PC0_158") (pintype "passive"))
      (node (ref "X4") (pin "10") (pinfunction "KL_10") (pintype "passive"))
    )
    (net (code "119") (name "Net-(U3-SPI1_NPCS1{slash}A24{slash}PC5)") (class "Default")
      (node (ref "U3") (pin "67") (pinfunction "SPI1_NPCS1/A24/PC5_67") (pintype "passive"))
      (node (ref "X4") (pin "14") (pinfunction "KL_14") (pintype "passive"))
    )
    (net (code "120") (name "Net-(U3-SPI1_NPCS2{slash}A23{slash}PC4)") (class "Default")
      (node (ref "U3") (pin "62") (pinfunction "SPI1_NPCS2/A23/PC4_62") (pintype "passive"))
      (node (ref "X4") (pin "15") (pinfunction "KL_15") (pintype "passive"))
    )
    (net (code "121") (name "Net-(U3-TCK)") (class "Default")
      (node (ref "RN2") (pin "1") (pinfunction "1_1") (pintype "passive"))
      (node (ref "SV1") (pin "9") (pinfunction "9_9") (pintype "passive"))
      (node (ref "U3") (pin "34") (pinfunction "TCK_34") (pintype "passive"))
    )
    (net (code "122") (name "Net-(U3-TCLK1{slash}TXD1{slash}PB6)") (class "Default")
      (node (ref "U3") (pin "17") (pinfunction "TCLK1/TXD1/PB6_17") (pintype "passive"))
      (node (ref "X4") (pin "22") (pinfunction "KL_22") (pintype "passive"))
    )
    (net (code "123") (name "Net-(U3-TCLK2{slash}RXD1{slash}PB7)") (class "Default")
      (node (ref "U3") (pin "18") (pinfunction "TCLK2/RXD1/PB7_18") (pintype "passive"))
      (node (ref "X4") (pin "21") (pinfunction "KL_21") (pintype "passive"))
    )
    (net (code "124") (name "Net-(U3-TCLK3{slash}TK0{slash}PB16)") (class "Default")
      (node (ref "U3") (pin "23") (pinfunction "TCLK3/TK0/PB16_23") (pintype "passive"))
      (node (ref "X4") (pin "18") (pinfunction "KL_18") (pintype "passive"))
    )
    (net (code "125") (name "Net-(U3-TCLK4{slash}TF0{slash}PB17)") (class "Default")
      (node (ref "U3") (pin "26") (pinfunction "TCLK4/TF0/PB17_26") (pintype "passive"))
      (node (ref "X4") (pin "17") (pinfunction "KL_17") (pintype "passive"))
    )
    (net (code "126") (name "Net-(U3-TDO)") (class "Default")
      (node (ref "SV1") (pin "13") (pinfunction "13_13") (pintype "passive"))
      (node (ref "U3") (pin "29") (pinfunction "TDO_29") (pintype "passive"))
    )
    (net (code "127") (name "Net-(U3-TIOA3{slash}SPI1_MISO{slash}PB0)") (class "Default")
      (node (ref "U3") (pin "9") (pinfunction "TIOA3/SPI1_MISO/PB0_9") (pintype "passive"))
      (node (ref "X4") (pin "28") (pinfunction "KL_28") (pintype "passive"))
    )
    (net (code "128") (name "Net-(U3-TIOA4{slash}SPI1_SPCK{slash}PB2)") (class "Default")
      (node (ref "U3") (pin "11") (pinfunction "TIOA4/SPI1_SPCK/PB2_11") (pintype "passive"))
      (node (ref "X4") (pin "26") (pinfunction "KL_26") (pintype "passive"))
    )
    (net (code "129") (name "Net-(U3-TIOA5{slash}SPI1_NPCS0{slash}PB3)") (class "Default")
      (node (ref "U3") (pin "12") (pinfunction "TIOA5/SPI1_NPCS0/PB3_12") (pintype "passive"))
      (node (ref "X4") (pin "25") (pinfunction "KL_25") (pintype "passive"))
    )
    (net (code "130") (name "Net-(U3-TIOB3{slash}SPI1_MOSI{slash}PB1)") (class "Default")
      (node (ref "U3") (pin "10") (pinfunction "TIOB3/SPI1_MOSI/PB1_10") (pintype "passive"))
      (node (ref "X4") (pin "27") (pinfunction "KL_27") (pintype "passive"))
    )
    (net (code "131") (name "Net-(U3-TIOB4{slash}TD0{slash}PB18)") (class "Default")
      (node (ref "U3") (pin "27") (pinfunction "TIOB4/TD0/PB18_27") (pintype "passive"))
      (node (ref "X4") (pin "13") (pinfunction "KL_13") (pintype "passive"))
    )
    (net (code "132") (name "Net-(U3-TIOB5{slash}RD0{slash}PB19)") (class "Default")
      (node (ref "U3") (pin "28") (pinfunction "TIOB5/RD0/PB19_28") (pintype "passive"))
      (node (ref "X4") (pin "11") (pinfunction "KL_11") (pintype "passive"))
    )
    (net (code "133") (name "Net-(U3-TST)") (class "Default")
      (node (ref "R14") (pin "2") (pinfunction "2_2") (pintype "passive"))
      (node (ref "U3") (pin "42") (pinfunction "TST_42") (pintype "passive"))
    )
    (net (code "134") (name "Net-(U3-TXD0{slash}PB4)") (class "Default")
      (node (ref "U3") (pin "15") (pinfunction "TXD0/PB4_15") (pintype "passive"))
      (node (ref "X4") (pin "24") (pinfunction "KL_24") (pintype "passive"))
    )
    (net (code "135") (name "Net-(U3-TXD2{slash}PB8)") (class "Default")
      (node (ref "U3") (pin "19") (pinfunction "TXD2/PB8_19") (pintype "passive"))
      (node (ref "X4") (pin "20") (pinfunction "KL_20") (pintype "passive"))
    )
    (net (code "136") (name "Net-(U3-VDDBU)") (class "Default")
      (node (ref "C27") (pin "1") (pinfunction "1_1") (pintype "passive"))
      (node (ref "C35") (pin "2") (pinfunction "2_2") (pintype "passive"))
      (node (ref "R19") (pin "2") (pinfunction "2_2") (pintype "passive"))
      (node (ref "R21") (pin "2") (pinfunction "2_2") (pintype "passive"))
      (node (ref "U3") (pin "47") (pinfunction "VDDBU_47") (pintype "passive"))
      (node (ref "VR1") (pin "5") (pinfunction "OUT_5") (pintype "passive"))
    )
    (net (code "137") (name "Net-(U3-WKUP)") (class "Default")
      (node (ref "R21") (pin "1") (pinfunction "1_1") (pintype "passive"))
      (node (ref "U3") (pin "48") (pinfunction "WKUP_48") (pintype "passive"))
      (node (ref "WAKE") (pin "3") (pinfunction "3_3") (pintype "passive"))
      (node (ref "WAKE") (pin "4") (pinfunction "4_4") (pintype "passive"))
    )
    (net (code "138") (name "Net-(U3-XIN)") (class "Default")
      (node (ref "C9") (pin "2") (pinfunction "2_2") (pintype "passive"))
      (node (ref "U3") (pin "149") (pinfunction "XIN_149") (pintype "passive"))
      (node (ref "X3") (pin "1") (pinfunction "X1_1") (pintype "passive"))
    )
    (net (code "139") (name "Net-(U3-XIN32)") (class "Default")
      (node (ref "C11") (pin "2") (pinfunction "2_2") (pintype "passive"))
      (node (ref "Q1") (pin "1") (pinfunction "1_1") (pintype "passive"))
      (node (ref "U3") (pin "46") (pinfunction "XIN32_46") (pintype "passive"))
    )
    (net (code "140") (name "Net-(U3-XOUT)") (class "Default")
      (node (ref "C8") (pin "2") (pinfunction "2_2") (pintype "passive"))
      (node (ref "U3") (pin "150") (pinfunction "XOUT_150") (pintype "passive"))
      (node (ref "X3") (pin "2") (pinfunction "X2_2") (pintype "passive"))
    )
    (net (code "141") (name "Net-(U3-XOUT32)") (class "Default")
      (node (ref "C10") (pin "2") (pinfunction "2_2") (pintype "passive"))
      (node (ref "Q1") (pin "2") (pinfunction "2_2") (pintype "passive"))
      (node (ref "U3") (pin "45") (pinfunction "XOUT32_45") (pintype "passive"))
    )
    (net (code "142") (name "Net-(VR1-EN)") (class "Default")
      (node (ref "R23") (pin "2") (pinfunction "2_2") (pintype "passive"))
      (node (ref "VR1") (pin "1") (pinfunction "IN_1") (pintype "passive"))
      (node (ref "VR1") (pin "3") (pinfunction "EN_3") (pintype "passive"))
    )
    (net (code "143") (name "unconnected-(BATT1-PadV1)") (class "Default")
      (node (ref "BATT1") (pin "V1") (pinfunction "V1_V1") (pintype "passive"))
    )
    (net (code "144") (name "unconnected-(IC2A-DQ0-Pad2)") (class "Default")
      (node (ref "IC2") (pin "2") (pinfunction "DQ0_2") (pintype "passive"))
    )
    (net (code "145") (name "unconnected-(IC2A-DQ1-Pad4)") (class "Default")
      (node (ref "IC2") (pin "4") (pinfunction "DQ1_4") (pintype "passive"))
    )
    (net (code "146") (name "unconnected-(IC2A-DQ2-Pad5)") (class "Default")
      (node (ref "IC2") (pin "5") (pinfunction "DQ2_5") (pintype "passive"))
    )
    (net (code "147") (name "unconnected-(IC2A-DQ3-Pad7)") (class "Default")
      (node (ref "IC2") (pin "7") (pinfunction "DQ3_7") (pintype "passive"))
    )
    (net (code "148") (name "unconnected-(IC2A-DQ4-Pad8)") (class "Default")
      (node (ref "IC2") (pin "8") (pinfunction "DQ4_8") (pintype "passive"))
    )
    (net (code "149") (name "unconnected-(IC2A-DQ5-Pad10)") (class "Default")
      (node (ref "IC2") (pin "10") (pinfunction "DQ5_10") (pintype "passive"))
    )
    (net (code "150") (name "unconnected-(IC2A-DQ6-Pad11)") (class "Default")
      (node (ref "IC2") (pin "11") (pinfunction "DQ6_11") (pintype "passive"))
    )
    (net (code "151") (name "unconnected-(IC2A-DQ7-Pad13)") (class "Default")
      (node (ref "IC2") (pin "13") (pinfunction "DQ7_13") (pintype "passive"))
    )
    (net (code "152") (name "unconnected-(IC2A-DQ8-Pad42)") (class "Default")
      (node (ref "IC2") (pin "42") (pinfunction "DQ8_42") (pintype "passive"))
    )
    (net (code "153") (name "unconnected-(IC2A-DQ9-Pad44)") (class "Default")
      (node (ref "IC2") (pin "44") (pinfunction "DQ9_44") (pintype "passive"))
    )
    (net (code "154") (name "unconnected-(IC2A-DQ10-Pad45)") (class "Default")
      (node (ref "IC2") (pin "45") (pinfunction "DQ10_45") (pintype "passive"))
    )
    (net (code "155") (name "unconnected-(IC2A-DQ11-Pad47)") (class "Default")
      (node (ref "IC2") (pin "47") (pinfunction "DQ11_47") (pintype "passive"))
    )
    (net (code "156") (name "unconnected-(IC2A-DQ12-Pad48)") (class "Default")
      (node (ref "IC2") (pin "48") (pinfunction "DQ12_48") (pintype "passive"))
    )
    (net (code "157") (name "unconnected-(IC2A-DQ13-Pad50)") (class "Default")
      (node (ref "IC2") (pin "50") (pinfunction "DQ13_50") (pintype "passive"))
    )
    (net (code "158") (name "unconnected-(IC2A-DQ14-Pad51)") (class "Default")
      (node (ref "IC2") (pin "51") (pinfunction "DQ14_51") (pintype "passive"))
    )
    (net (code "159") (name "unconnected-(IC2A-DQ15-Pad53)") (class "Default")
      (node (ref "IC2") (pin "53") (pinfunction "DQ15_53") (pintype "passive"))
    )
    (net (code "160") (name "unconnected-(IC2A-NC-Pad40)") (class "Default")
      (node (ref "IC2") (pin "40") (pinfunction "NC_40") (pintype "passive"))
    )
    (net (code "161") (name "unconnected-(J4-Pad3)") (class "Default")
      (node (ref "J4") (pin "3") (pinfunction "3_3") (pintype "passive"))
    )
    (net (code "162") (name "unconnected-(R4A-Pad1)") (class "Default")
      (node (ref "R4A") (pin "1") (pinfunction "1_1") (pintype "passive"))
    )
    (net (code "163") (name "unconnected-(R5A-Pad1)") (class "Default")
      (node (ref "R5A") (pin "1") (pinfunction "1_1") (pintype "passive"))
    )
    (net (code "164") (name "unconnected-(R35-Pad1)") (class "Default")
      (node (ref "R35") (pin "1") (pinfunction "1_1") (pintype "passive"))
    )
    (net (code "165") (name "unconnected-(R36-Pad1)") (class "Default")
      (node (ref "R36") (pin "1") (pinfunction "1_1") (pintype "passive"))
    )
    (net (code "166") (name "unconnected-(U$1-INTRP-PadP$32)") (class "Default")
      (node (ref "U$1") (pin "P$32") (pinfunction "INTRP_P$32") (pintype "passive"))
    )
    (net (code "167") (name "unconnected-(U$1-MDC-PadP$19)") (class "Default")
      (node (ref "U$1") (pin "P$19") (pinfunction "MDC_P$19") (pintype "passive"))
    )
    (net (code "168") (name "unconnected-(U$1-MDIO-PadP$18)") (class "Default")
      (node (ref "U$1") (pin "P$18") (pinfunction "MDIO_P$18") (pintype "passive"))
    )
    (net (code "169") (name "unconnected-(U$1-NC_1-PadP$44)") (class "Default")
      (node (ref "U$1") (pin "P$44") (pinfunction "NC_1_P$44") (pintype "passive"))
    )
    (net (code "170") (name "unconnected-(U$1-NC_2-PadP$45)") (class "Default")
      (node (ref "U$1") (pin "P$45") (pinfunction "NC_2_P$45") (pintype "passive"))
    )
    (net (code "171") (name "unconnected-(U$1-NC_3-PadP$46)") (class "Default")
      (node (ref "U$1") (pin "P$46") (pinfunction "NC_3_P$46") (pintype "passive"))
    )
    (net (code "172") (name "unconnected-(U$1-NC_4-PadP$48)") (class "Default")
      (node (ref "U$1") (pin "P$48") (pinfunction "NC_4_P$48") (pintype "passive"))
    )
    (net (code "173") (name "unconnected-(U$1-RX--PadP$9)") (class "Default")
      (node (ref "U$1") (pin "P$9") (pinfunction "RX-_P$9") (pintype "passive"))
    )
    (net (code "174") (name "unconnected-(U$1-RXC-PadP$28)") (class "Default")
      (node (ref "U$1") (pin "P$28") (pinfunction "RXC_P$28") (pintype "passive"))
    )
    (net (code "175") (name "unconnected-(U$1-RXD2{slash}PHYAD1-PadP$21)") (class "Default")
      (node (ref "U$1") (pin "P$21") (pinfunction "RXD2/PHYAD1_P$21") (pintype "passive"))
    )
    (net (code "176") (name "unconnected-(U$1-RXD3{slash}PHYAD0-PadP$20)") (class "Default")
      (node (ref "U$1") (pin "P$20") (pinfunction "RXD3/PHYAD0_P$20") (pintype "passive"))
    )
    (net (code "177") (name "unconnected-(U$1-TXC-PadP$33)") (class "Default")
      (node (ref "U$1") (pin "P$33") (pinfunction "TXC_P$33") (pintype "passive"))
    )
    (net (code "178") (name "unconnected-(U$1-TXD2-PadP$38)") (class "Default")
      (node (ref "U$1") (pin "P$38") (pinfunction "TXD2_P$38") (pintype "passive"))
    )
    (net (code "179") (name "unconnected-(U$1-TXD3-PadP$39)") (class "Default")
      (node (ref "U$1") (pin "P$39") (pinfunction "TXD3_P$39") (pintype "passive"))
    )
    (net (code "180") (name "unconnected-(U$1-XO-PadP$14)") (class "Default")
      (node (ref "U$1") (pin "P$14") (pinfunction "XO_P$14") (pintype "passive"))
    )
    (net (code "181") (name "unconnected-(U$2-PadGND)") (class "Default")
      (node (ref "U$2") (pin "GND") (pinfunction "GND_GND") (pintype "passive"))
    )
    (net (code "182") (name "unconnected-(U3-A10-Pad87)") (class "Default")
      (node (ref "U3") (pin "87") (pinfunction "A10_87") (pintype "passive"))
    )
    (net (code "183") (name "unconnected-(U3-A14-Pad83)") (class "Default")
      (node (ref "U3") (pin "83") (pinfunction "A14_83") (pintype "passive"))
    )
    (net (code "184") (name "unconnected-(U3-A15-Pad82)") (class "Default")
      (node (ref "U3") (pin "82") (pinfunction "A15_82") (pintype "passive"))
    )
    (net (code "185") (name "unconnected-(U3-A18-Pad79)") (class "Default")
      (node (ref "U3") (pin "79") (pinfunction "A18_79") (pintype "passive"))
    )
    (net (code "186") (name "unconnected-(U3-A19-Pad76)") (class "Default")
      (node (ref "U3") (pin "76") (pinfunction "A19_76") (pintype "passive"))
    )
    (net (code "187") (name "unconnected-(U3-A20-Pad75)") (class "Default")
      (node (ref "U3") (pin "75") (pinfunction "A20_75") (pintype "passive"))
    )
    (net (code "188") (name "unconnected-(U3-A21-Pad74)") (class "Default")
      (node (ref "U3") (pin "74") (pinfunction "A21_74") (pintype "passive"))
    )
    (net (code "189") (name "unconnected-(U3-A22-Pad73)") (class "Default")
      (node (ref "U3") (pin "73") (pinfunction "A22_73") (pintype "passive"))
    )
    (net (code "190") (name "unconnected-(U3-CFCE1{slash}TIOB2{slash}PC6-Pad63)") (class "Default")
      (node (ref "U3") (pin "63") (pinfunction "CFCE1/TIOB2/PC6_63") (pintype "passive"))
    )
    (net (code "191") (name "unconnected-(U3-CFCE2{slash}TIOB1{slash}PC7-Pad64)") (class "Default")
      (node (ref "U3") (pin "64") (pinfunction "CFCE2/TIOB1/PC7_64") (pintype "passive"))
    )
    (net (code "192") (name "unconnected-(U3-CFIOW{slash}NBS3{slash}NWR3-Pad101)") (class "Default")
      (node (ref "U3") (pin "101") (pinfunction "CFIOW/NBS3/NWR3_101") (pintype "passive"))
    )
    (net (code "193") (name "unconnected-(U3-CFOE{slash}NRD-Pad69)") (class "Default")
      (node (ref "U3") (pin "69") (pinfunction "CFOE/NRD_69") (pintype "passive"))
    )
    (net (code "194") (name "unconnected-(U3-CFWE{slash}NWE{slash}NWR0-Pad70)") (class "Default")
      (node (ref "U3") (pin "70") (pinfunction "CFWE/NWE/NWR0_70") (pintype "passive"))
    )
    (net (code "195") (name "unconnected-(U3-CTS3{slash}A25_CFRNW{slash}PC10-Pad58)") (class "Default")
      (node (ref "U3") (pin "58") (pinfunction "CTS3/A25_CFRNW/PC10_58") (pintype "passive"))
    )
    (net (code "196") (name "unconnected-(U3-D0-Pad106)") (class "Default")
      (node (ref "U3") (pin "106") (pinfunction "D0_106") (pintype "passive"))
    )
    (net (code "197") (name "unconnected-(U3-D1-Pad107)") (class "Default")
      (node (ref "U3") (pin "107") (pinfunction "D1_107") (pintype "passive"))
    )
    (net (code "198") (name "unconnected-(U3-D2-Pad108)") (class "Default")
      (node (ref "U3") (pin "108") (pinfunction "D2_108") (pintype "passive"))
    )
    (net (code "199") (name "unconnected-(U3-D3-Pad109)") (class "Default")
      (node (ref "U3") (pin "109") (pinfunction "D3_109") (pintype "passive"))
    )
    (net (code "200") (name "unconnected-(U3-D4-Pad110)") (class "Default")
      (node (ref "U3") (pin "110") (pinfunction "D4_110") (pintype "passive"))
    )
    (net (code "201") (name "unconnected-(U3-D5-Pad111)") (class "Default")
      (node (ref "U3") (pin "111") (pinfunction "D5_111") (pintype "passive"))
    )
    (net (code "202") (name "unconnected-(U3-D6-Pad112)") (class "Default")
      (node (ref "U3") (pin "112") (pinfunction "D6_112") (pintype "passive"))
    )
    (net (code "203") (name "unconnected-(U3-D7-Pad118)") (class "Default")
      (node (ref "U3") (pin "118") (pinfunction "D7_118") (pintype "passive"))
    )
    (net (code "204") (name "unconnected-(U3-D8-Pad119)") (class "Default")
      (node (ref "U3") (pin "119") (pinfunction "D8_119") (pintype "passive"))
    )
    (net (code "205") (name "unconnected-(U3-D9-Pad120)") (class "Default")
      (node (ref "U3") (pin "120") (pinfunction "D9_120") (pintype "passive"))
    )
    (net (code "206") (name "unconnected-(U3-D10-Pad121)") (class "Default")
      (node (ref "U3") (pin "121") (pinfunction "D10_121") (pintype "passive"))
    )
    (net (code "207") (name "unconnected-(U3-D11-Pad122)") (class "Default")
      (node (ref "U3") (pin "122") (pinfunction "D11_122") (pintype "passive"))
    )
    (net (code "208") (name "unconnected-(U3-D12-Pad123)") (class "Default")
      (node (ref "U3") (pin "123") (pinfunction "D12_123") (pintype "passive"))
    )
    (net (code "209") (name "unconnected-(U3-D13-Pad124)") (class "Default")
      (node (ref "U3") (pin "124") (pinfunction "D13_124") (pintype "passive"))
    )
    (net (code "210") (name "unconnected-(U3-D23{slash}PC23-Pad137)") (class "Default")
      (node (ref "U3") (pin "137") (pinfunction "D23/PC23_137") (pintype "passive"))
    )
    (net (code "211") (name "unconnected-(U3-D24{slash}PC24-Pad138)") (class "Default")
      (node (ref "U3") (pin "138") (pinfunction "D24/PC24_138") (pintype "passive"))
    )
    (net (code "212") (name "unconnected-(U3-D25{slash}PC25-Pad139)") (class "Default")
      (node (ref "U3") (pin "139") (pinfunction "D25/PC25_139") (pintype "passive"))
    )
    (net (code "213") (name "unconnected-(U3-D26{slash}PC26-Pad140)") (class "Default")
      (node (ref "U3") (pin "140") (pinfunction "D26/PC26_140") (pintype "passive"))
    )
    (net (code "214") (name "unconnected-(U3-D27{slash}PC27-Pad141)") (class "Default")
      (node (ref "U3") (pin "141") (pinfunction "D27/PC27_141") (pintype "passive"))
    )
    (net (code "215") (name "unconnected-(U3-D28{slash}PC28-Pad142)") (class "Default")
      (node (ref "U3") (pin "142") (pinfunction "D28/PC28_142") (pintype "passive"))
    )
    (net (code "216") (name "unconnected-(U3-EF100{slash}D21{slash}PC21-Pad135)") (class "Default")
      (node (ref "U3") (pin "135") (pinfunction "EF100/D21/PC21_135") (pintype "passive"))
    )
    (net (code "217") (name "unconnected-(U3-ISI_D0{slash}RK0{slash}PB20-Pad163)") (class "Default")
      (node (ref "U3") (pin "163") (pinfunction "ISI_D0/RK0/PB20_163") (pintype "passive"))
    )
    (net (code "218") (name "unconnected-(U3-ISI_D1{slash}RF0{slash}PB21-Pad164)") (class "Default")
      (node (ref "U3") (pin "164") (pinfunction "ISI_D1/RF0/PB21_164") (pintype "passive"))
    )
    (net (code "219") (name "unconnected-(U3-ISI_D2{slash}DSR0{slash}PB22-Pad165)") (class "Default")
      (node (ref "U3") (pin "165") (pinfunction "ISI_D2/DSR0/PB22_165") (pintype "passive"))
    )
    (net (code "220") (name "unconnected-(U3-ISI_D3{slash}DCD0{slash}PB23-Pad166)") (class "Default")
      (node (ref "U3") (pin "166") (pinfunction "ISI_D3/DCD0/PB23_166") (pintype "passive"))
    )
    (net (code "221") (name "unconnected-(U3-ISI_D4{slash}DTR0{slash}PB24-Pad167)") (class "Default")
      (node (ref "U3") (pin "167") (pinfunction "ISI_D4/DTR0/PB24_167") (pintype "passive"))
    )
    (net (code "222") (name "unconnected-(U3-ISI_D5{slash}RI0{slash}PB25-Pad168)") (class "Default")
      (node (ref "U3") (pin "168") (pinfunction "ISI_D5/RI0/PB25_168") (pintype "passive"))
    )
    (net (code "223") (name "unconnected-(U3-ISI_D6{slash}RTS0{slash}PB26-Pad171)") (class "Default")
      (node (ref "U3") (pin "171") (pinfunction "ISI_D6/RTS0/PB26_171") (pintype "passive"))
    )
    (net (code "224") (name "unconnected-(U3-ISI_D7{slash}CTS0{slash}PB27-Pad172)") (class "Default")
      (node (ref "U3") (pin "172") (pinfunction "ISI_D7/CTS0/PB27_172") (pintype "passive"))
    )
    (net (code "225") (name "unconnected-(U3-ISI_D8{slash}TXD3{slash}PB10-Pad161)") (class "Default")
      (node (ref "U3") (pin "161") (pinfunction "ISI_D8/TXD3/PB10_161") (pintype "passive"))
    )
    (net (code "226") (name "unconnected-(U3-ISI_D9{slash}RXD3{slash}PB11-Pad162)") (class "Default")
      (node (ref "U3") (pin "162") (pinfunction "ISI_D9/RXD3/PB11_162") (pintype "passive"))
    )
    (net (code "227") (name "unconnected-(U3-ISI_HSYNC{slash}PCK0{slash}PB30-Pad177)") (class "Default")
      (node (ref "U3") (pin "177") (pinfunction "ISI_HSYNC/PCK0/PB30_177") (pintype "passive"))
    )
    (net (code "228") (name "unconnected-(U3-ISI_MCK{slash}PCK1{slash}PB31-Pad178)") (class "Default")
      (node (ref "U3") (pin "178") (pinfunction "ISI_MCK/PCK1/PB31_178") (pintype "passive"))
    )
    (net (code "229") (name "unconnected-(U3-ISI_PCK{slash}RTS1{slash}PB28-Pad175)") (class "Default")
      (node (ref "U3") (pin "175") (pinfunction "ISI_PCK/RTS1/PB28_175") (pintype "passive"))
    )
    (net (code "230") (name "unconnected-(U3-ISI_VSYNC{slash}CTS1{slash}PB29-Pad176)") (class "Default")
      (node (ref "U3") (pin "176") (pinfunction "ISI_VSYNC/CTS1/PB29_176") (pintype "passive"))
    )
    (net (code "231") (name "unconnected-(U3-NANDOE-Pad71)") (class "Default")
      (node (ref "U3") (pin "71") (pinfunction "NANDOE_71") (pintype "passive"))
    )
    (net (code "232") (name "unconnected-(U3-NANDWE-Pad72)") (class "Default")
      (node (ref "U3") (pin "72") (pinfunction "NANDWE_72") (pintype "passive"))
    )
    (net (code "233") (name "unconnected-(U3-NC@152-Pad152)") (class "Default")
      (node (ref "U3") (pin "152") (pinfunction "NC@152_152") (pintype "passive"))
    )
    (net (code "234") (name "unconnected-(U3-NCS6{slash}FIQ{slash}PC13-Pad56)") (class "Default")
      (node (ref "U3") (pin "56") (pinfunction "NCS6/FIQ/PC13_56") (pintype "passive"))
    )
    (net (code "235") (name "unconnected-(U3-NCSO-Pad68)") (class "Default")
      (node (ref "U3") (pin "68") (pinfunction "NCSO_68") (pintype "passive"))
    )
    (net (code "236") (name "unconnected-(U3-PA4{slash}RTS2{slash}MCDB2-Pad183)") (class "Default")
      (node (ref "U3") (pin "183") (pinfunction "PA4/RTS2/MCDB2_183") (pintype "passive"))
    )
    (net (code "237") (name "unconnected-(U3-PA5{slash}CTS2{slash}MCDB1-Pad184)") (class "Default")
      (node (ref "U3") (pin "184") (pinfunction "PA5/CTS2/MCDB1_184") (pintype "passive"))
    )
    (net (code "238") (name "unconnected-(U3-PA20{slash}EMDC-Pad205)") (class "Default")
      (node (ref "U3") (pin "205") (pinfunction "PA20/EMDC_205") (pintype "passive"))
    )
    (net (code "239") (name "unconnected-(U3-PA21{slash}EMDIO-Pad206)") (class "Default")
      (node (ref "U3") (pin "206") (pinfunction "PA21/EMDIO_206") (pintype "passive"))
    )
    (net (code "240") (name "unconnected-(U3-PA22{slash}ADTRG{slash}ETXER-Pad207)") (class "Default")
      (node (ref "U3") (pin "207") (pinfunction "PA22/ADTRG/ETXER_207") (pintype "passive"))
    )
    (net (code "241") (name "unconnected-(U3-PA25{slash}TLCK0{slash}ERX2-Pad2)") (class "Default")
      (node (ref "U3") (pin "2") (pinfunction "PA25/TLCK0/ERX2_2") (pintype "passive"))
    )
    (net (code "242") (name "unconnected-(U3-PA27{slash}TIOA1{slash}ERXCK-Pad4)") (class "Default")
      (node (ref "U3") (pin "4") (pinfunction "PA27/TIOA1/ERXCK_4") (pintype "passive"))
    )
    (net (code "243") (name "unconnected-(U3-PA28{slash}TIOA2{slash}ECRS-Pad7)") (class "Default")
      (node (ref "U3") (pin "7") (pinfunction "PA28/TIOA2/ECRS_7") (pintype "passive"))
    )
    (net (code "244") (name "unconnected-(U3-PA29{slash}SCK1{slash}ECOL-Pad8)") (class "Default")
      (node (ref "U3") (pin "8") (pinfunction "PA29/SCK1/ECOL_8") (pintype "passive"))
    )
    (net (code "245") (name "unconnected-(U3-RTS3{slash}NCS4_CFCS0{slash}PC8-Pad61)") (class "Default")
      (node (ref "U3") (pin "61") (pinfunction "RTS3/NCS4_CFCS0/PC8_61") (pintype "passive"))
    )
    (net (code "246") (name "unconnected-(U3-SPI0_NPCS1{slash}NCS2{slash}PC11-Pad57)") (class "Default")
      (node (ref "U3") (pin "57") (pinfunction "SPI0_NPCS1/NCS2/PC11_57") (pintype "passive"))
    )
    (net (code "247") (name "unconnected-(U3-SPI0_NPCS2{slash}D16{slash}PC16-Pad128)") (class "Default")
      (node (ref "U3") (pin "128") (pinfunction "SPI0_NPCS2/D16/PC16_128") (pintype "passive"))
    )
    (net (code "248") (name "unconnected-(U3-SPI0_NPCS3{slash}D17{slash}PC17-Pad129)") (class "Default")
      (node (ref "U3") (pin "129") (pinfunction "SPI0_NPCS3/D17/PC17_129") (pintype "passive"))
    )
    (net (code "249") (name "unconnected-(U3-SPI1_NPCS1{slash}D18{slash}PC18-Pad130)") (class "Default")
      (node (ref "U3") (pin "130") (pinfunction "SPI1_NPCS1/D18/PC18_130") (pintype "passive"))
    )
    (net (code "250") (name "unconnected-(U3-SPI1_NPCS2{slash}D19{slash}PC19-Pad131)") (class "Default")
      (node (ref "U3") (pin "131") (pinfunction "SPI1_NPCS2/D19/PC19_131") (pintype "passive"))
    )
    (net (code "251") (name "unconnected-(U3-SPI1_NPCS3{slash}D20{slash}PC20-Pad134)") (class "Default")
      (node (ref "U3") (pin "134") (pinfunction "SPI1_NPCS3/D20/PC20_134") (pintype "passive"))
    )
    (net (code "252") (name "unconnected-(U3-TCLK5{slash}D22{slash}PC22-Pad136)") (class "Default")
      (node (ref "U3") (pin "136") (pinfunction "TCLK5/D22/PC22_136") (pintype "passive"))
    )
    (net (code "253") (name "unconnected-(U3-TIOB0{slash}NCS5_CFCS1{slash}PC9-Pad60)") (class "Default")
      (node (ref "U3") (pin "60") (pinfunction "TIOB0/NCS5_CFCS1/PC9_60") (pintype "passive"))
    )
    (net (code "254") (name "unconnected-(VR1-BYP-Pad4)") (class "Default")
      (node (ref "VR1") (pin "4") (pinfunction "BYP_4") (pintype "passive"))
    )
  )
)
